# 05_-_Gate_Drivers.net
KiCad netlist of a schematic drawn in Altium Designer
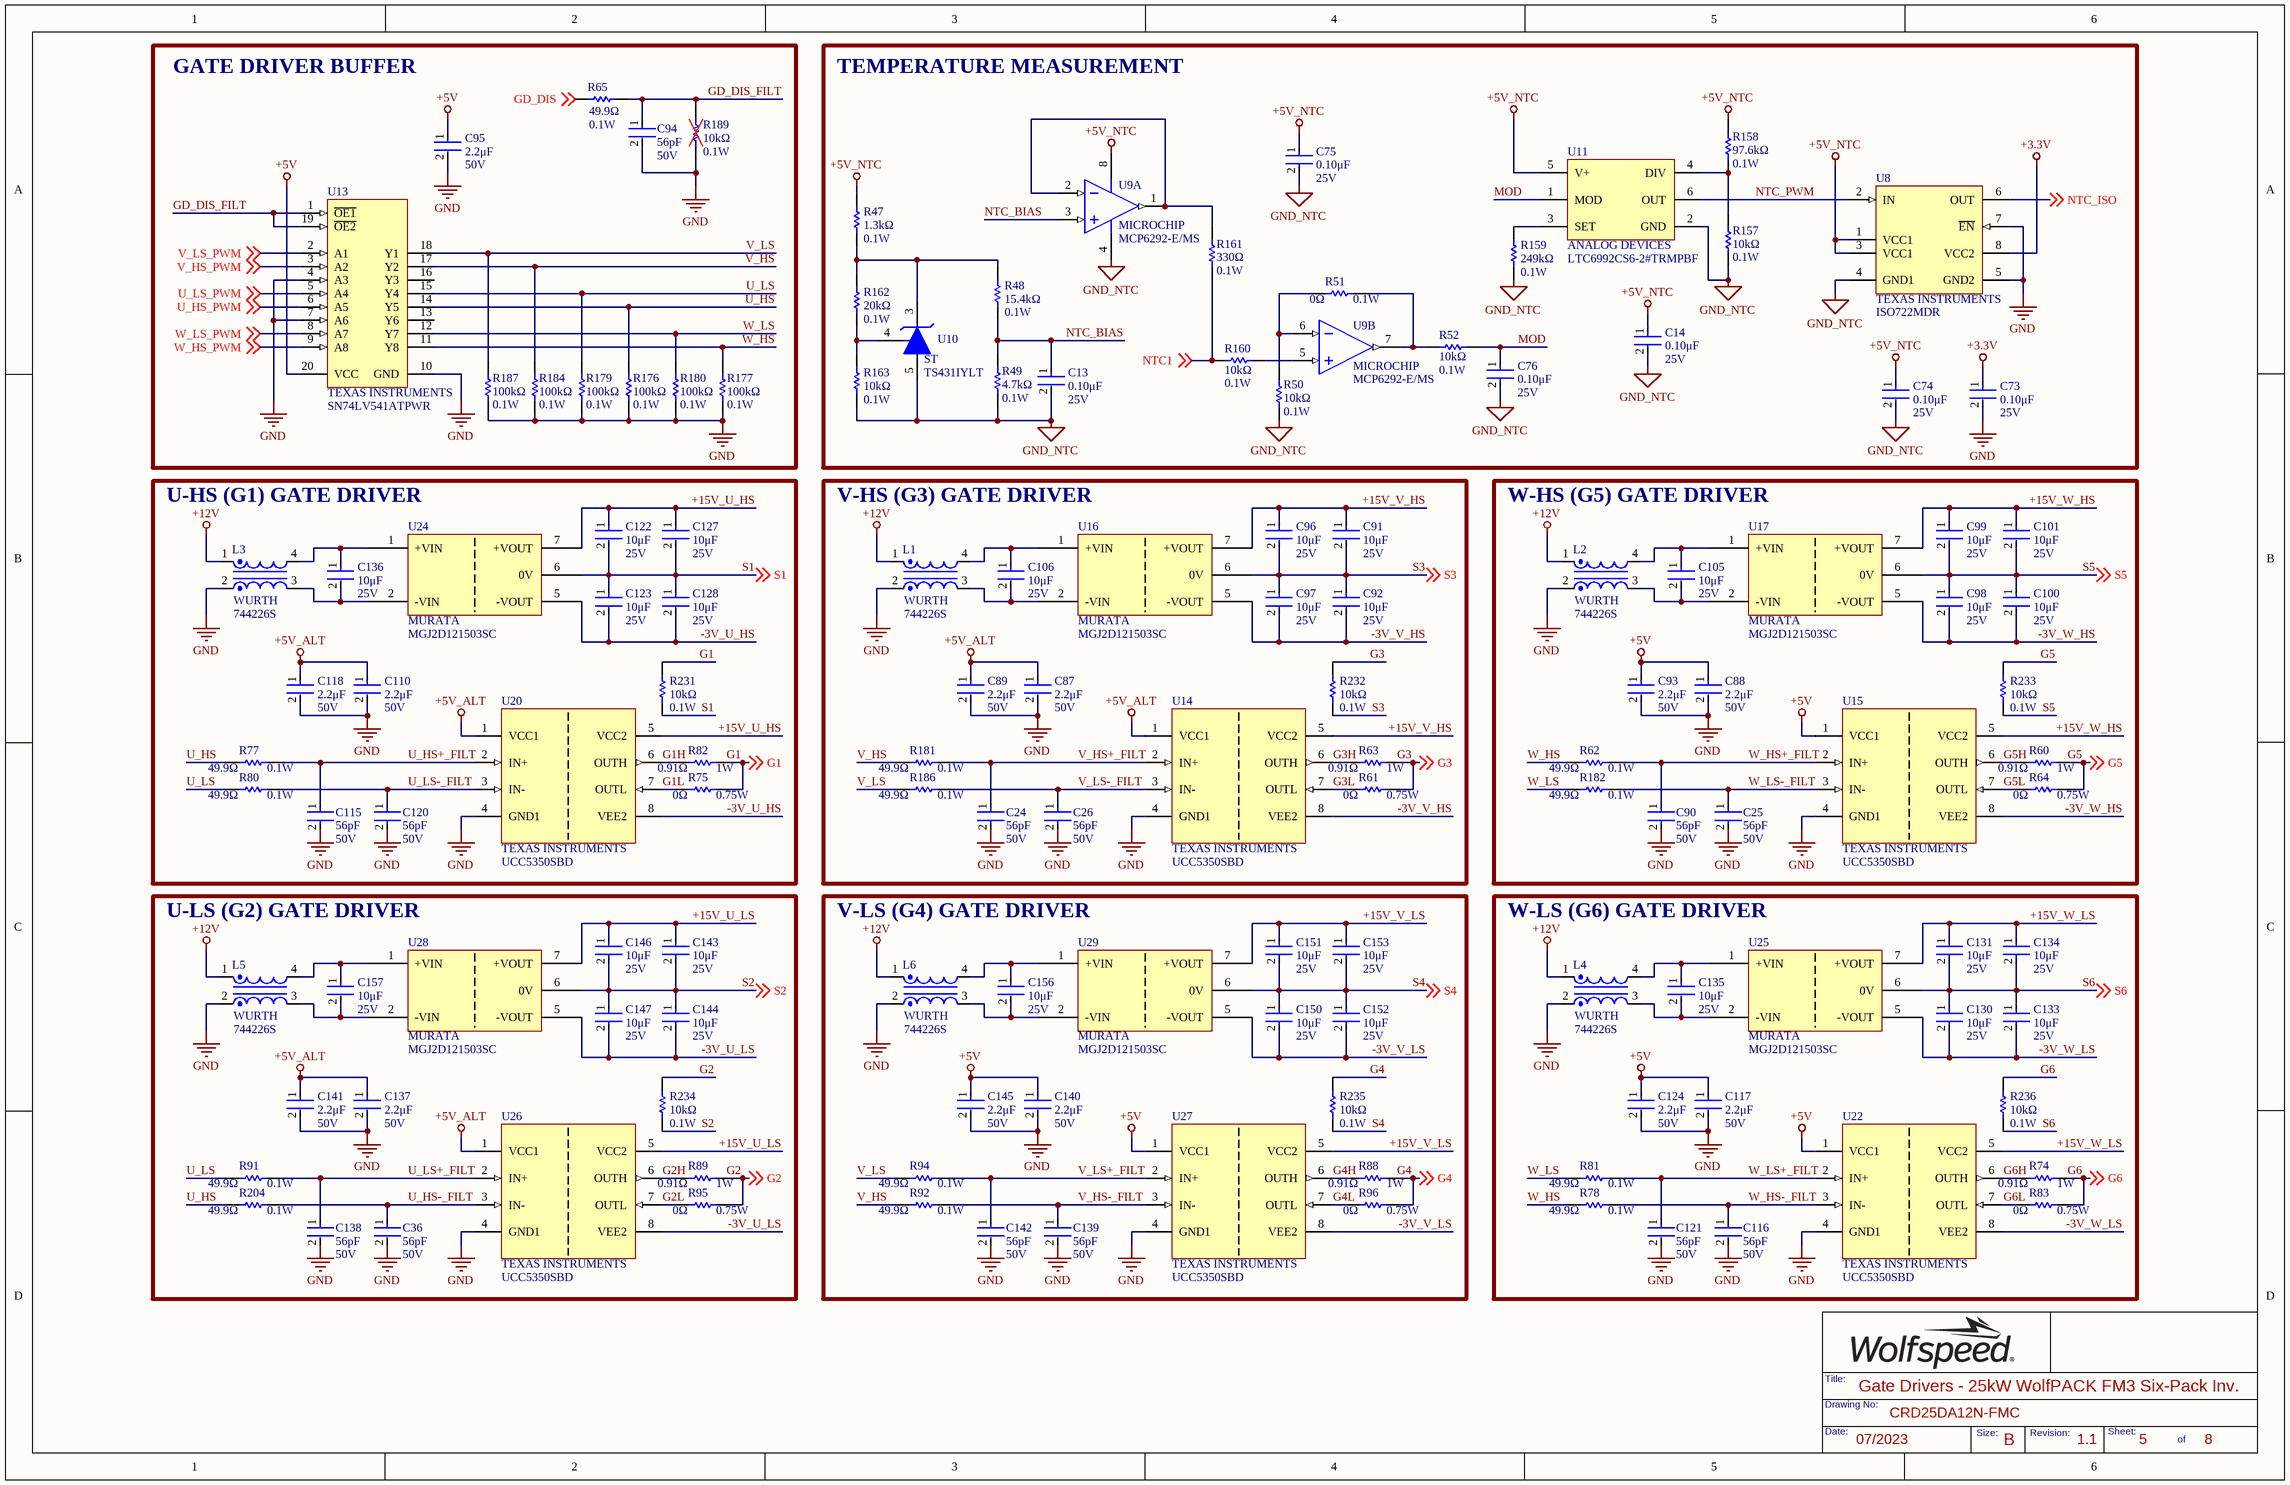
[diagram p0: 05 - Gate Drivers.SchDoc]

(export (version "E")
  (design (tool "Eeschema 10.0.6"))
  (components
    (comp (ref "C13")
      (value "C0603C104K3RACTU")
      (footprint "FP-C0603C-CF-IPC_B")
      (description "CAP CER 0.1UF 25V X7R 0603")
      (fields
        (field (name "VOLTAGE RATING") "25V")
        (field (name "OCTOPART") "https://octopart.com/c0603c104k3ractu-kemet-127541")
        (field (name "MANUFACTURER") "KEMET")
        (field (name "CAPACITANCE") "0.10μF")
      )
      (libsource (lib "Altium Content Vault") (part "b4654b650e69147ec39a6b967a45e02"))
    )
    (comp (ref "C14")
      (value "C0603C104K3RACTU")
      (footprint "FP-C0603C-CF-IPC_B")
      (description "CAP CER 0.1UF 25V X7R 0603")
      (fields
        (field (name "VOLTAGE RATING") "25V")
        (field (name "OCTOPART") "https://octopart.com/c0603c104k3ractu-kemet-127541")
        (field (name "MANUFACTURER") "KEMET")
        (field (name "CAPACITANCE") "0.10μF")
      )
      (libsource (lib "Altium Content Vault") (part "b4654b650e69147ec39a6b967a45e02"))
    )
    (comp (ref "C24")
      (value "CL10C560JB8NNNC")
      (footprint "FP-C0603C-CF-IPC_B")
      (description "CAP CER 56PF 50V C0G/NP0 0603")
      (fields
        (field (name "MANUFACTURER") "SAMSUNG")
        (field (name "TOLERANCE") "5%")
        (field (name "CAPACITANCE") "56pF")
        (field (name "VOLTAGE RATING") "50V")
      )
      (libsource (lib "Inverter_25kW") (part "CL10C560JB8NNNC"))
    )
    (comp (ref "C25")
      (value "CL10C560JB8NNNC")
      (footprint "FP-C0603C-CF-IPC_B")
      (description "CAP CER 56PF 50V C0G/NP0 0603")
      (fields
        (field (name "MANUFACTURER") "SAMSUNG")
        (field (name "TOLERANCE") "5%")
        (field (name "CAPACITANCE") "56pF")
        (field (name "VOLTAGE RATING") "50V")
      )
      (libsource (lib "Inverter_25kW") (part "CL10C560JB8NNNC"))
    )
    (comp (ref "C26")
      (value "CL10C560JB8NNNC")
      (footprint "FP-C0603C-CF-IPC_B")
      (description "CAP CER 56PF 50V C0G/NP0 0603")
      (fields
        (field (name "MANUFACTURER") "SAMSUNG")
        (field (name "TOLERANCE") "5%")
        (field (name "CAPACITANCE") "56pF")
        (field (name "VOLTAGE RATING") "50V")
      )
      (libsource (lib "Inverter_25kW") (part "CL10C560JB8NNNC"))
    )
    (comp (ref "C36")
      (value "CL10C560JB8NNNC")
      (footprint "FP-C0603C-CF-IPC_B")
      (description "CAP CER 56PF 50V C0G/NP0 0603")
      (fields
        (field (name "MANUFACTURER") "SAMSUNG")
        (field (name "TOLERANCE") "5%")
        (field (name "CAPACITANCE") "56pF")
        (field (name "VOLTAGE RATING") "50V")
      )
      (libsource (lib "Inverter_25kW") (part "CL10C560JB8NNNC"))
    )
    (comp (ref "C73")
      (value "C0603C104K3RACTU")
      (footprint "FP-C0603C-CF-IPC_B")
      (description "CAP CER 0.1UF 25V X7R 0603")
      (fields
        (field (name "VOLTAGE RATING") "25V")
        (field (name "OCTOPART") "https://octopart.com/c0603c104k3ractu-kemet-127541")
        (field (name "MANUFACTURER") "KEMET")
        (field (name "CAPACITANCE") "0.10μF")
      )
      (libsource (lib "Altium Content Vault") (part "b4654b650e69147ec39a6b967a45e02"))
    )
    (comp (ref "C74")
      (value "C0603C104K3RACTU")
      (footprint "FP-C0603C-CF-IPC_B")
      (description "CAP CER 0.1UF 25V X7R 0603")
      (fields
        (field (name "VOLTAGE RATING") "25V")
        (field (name "OCTOPART") "https://octopart.com/c0603c104k3ractu-kemet-127541")
        (field (name "MANUFACTURER") "KEMET")
        (field (name "CAPACITANCE") "0.10μF")
      )
      (libsource (lib "Altium Content Vault") (part "b4654b650e69147ec39a6b967a45e02"))
    )
    (comp (ref "C75")
      (value "C0603C104K3RACTU")
      (footprint "FP-C0603C-CF-IPC_B")
      (description "CAP CER 0.1UF 25V X7R 0603")
      (fields
        (field (name "VOLTAGE RATING") "25V")
        (field (name "OCTOPART") "https://octopart.com/c0603c104k3ractu-kemet-127541")
        (field (name "MANUFACTURER") "KEMET")
        (field (name "CAPACITANCE") "0.10μF")
      )
      (libsource (lib "Altium Content Vault") (part "b4654b650e69147ec39a6b967a45e02"))
    )
    (comp (ref "C76")
      (value "C0603C104K3RACTU")
      (footprint "FP-C0603C-CF-IPC_B")
      (description "CAP CER 0.1UF 25V X7R 0603")
      (fields
        (field (name "VOLTAGE RATING") "25V")
        (field (name "OCTOPART") "https://octopart.com/c0603c104k3ractu-kemet-127541")
        (field (name "MANUFACTURER") "KEMET")
        (field (name "CAPACITANCE") "0.10μF")
      )
      (libsource (lib "Altium Content Vault") (part "b4654b650e69147ec39a6b967a45e02"))
    )
    (comp (ref "C87")
      (value "GRT188R61H225ME13D")
      (footprint "FP-C0603C-CF-IPC_B")
      (description "CAP CER 2.2UF 50V X5R 0603")
      (fields
        (field (name "MANUFACTURER") "MURATA")
        (field (name "TOLERANCE") "20%")
        (field (name "VOLTAGE RATING") "50V")
        (field (name "CAPACITANCE") "2.2μF")
      )
      (libsource (lib "Inverter_25kW") (part "GRT188R61H225ME13D"))
    )
    (comp (ref "C88")
      (value "GRT188R61H225ME13D")
      (footprint "FP-C0603C-CF-IPC_B")
      (description "CAP CER 2.2UF 50V X5R 0603")
      (fields
        (field (name "MANUFACTURER") "MURATA")
        (field (name "TOLERANCE") "20%")
        (field (name "VOLTAGE RATING") "50V")
        (field (name "CAPACITANCE") "2.2μF")
      )
      (libsource (lib "Inverter_25kW") (part "GRT188R61H225ME13D"))
    )
    (comp (ref "C89")
      (value "GRT188R61H225ME13D")
      (footprint "FP-C0603C-CF-IPC_B")
      (description "CAP CER 2.2UF 50V X5R 0603")
      (fields
        (field (name "MANUFACTURER") "MURATA")
        (field (name "TOLERANCE") "20%")
        (field (name "VOLTAGE RATING") "50V")
        (field (name "CAPACITANCE") "2.2μF")
      )
      (libsource (lib "Inverter_25kW") (part "GRT188R61H225ME13D"))
    )
    (comp (ref "C90")
      (value "CL10C560JB8NNNC")
      (footprint "FP-C0603C-CF-IPC_B")
      (description "CAP CER 56PF 50V C0G/NP0 0603")
      (fields
        (field (name "MANUFACTURER") "SAMSUNG")
        (field (name "TOLERANCE") "5%")
        (field (name "CAPACITANCE") "56pF")
        (field (name "VOLTAGE RATING") "50V")
      )
      (libsource (lib "Inverter_25kW") (part "CL10C560JB8NNNC"))
    )
    (comp (ref "C91")
      (value "CL31B106KAHSFNE")
      (footprint "FP-CL31-IPC_B")
      (description "CAP CER 10UF 25V X7R 1206")
      (fields
        (field (name "VOLTAGE RATING") "25V")
        (field (name "TOLERANCE") "10%")
        (field (name "CAPACITANCE") "10μF")
        (field (name "MANUFACTURER") "SAMSUNG")
      )
      (libsource (lib "Altium Content Vault") (part "b4654b650e69147ec39a6b967a45e02"))
    )
    (comp (ref "C92")
      (value "CL31B106KAHSFNE")
      (footprint "FP-CL31-IPC_B")
      (description "CAP CER 10UF 25V X7R 1206")
      (fields
        (field (name "VOLTAGE RATING") "25V")
        (field (name "TOLERANCE") "10%")
        (field (name "CAPACITANCE") "10μF")
        (field (name "MANUFACTURER") "SAMSUNG")
      )
      (libsource (lib "Altium Content Vault") (part "b4654b650e69147ec39a6b967a45e02"))
    )
    (comp (ref "C93")
      (value "GRT188R61H225ME13D")
      (footprint "FP-C0603C-CF-IPC_B")
      (description "CAP CER 2.2UF 50V X5R 0603")
      (fields
        (field (name "MANUFACTURER") "MURATA")
        (field (name "TOLERANCE") "20%")
        (field (name "VOLTAGE RATING") "50V")
        (field (name "CAPACITANCE") "2.2μF")
      )
      (libsource (lib "Inverter_25kW") (part "GRT188R61H225ME13D"))
    )
    (comp (ref "C94")
      (value "CL10C560JB8NNNC")
      (footprint "FP-C0603C-CF-IPC_B")
      (description "CAP CER 56PF 50V C0G/NP0 0603")
      (fields
        (field (name "MANUFACTURER") "SAMSUNG")
        (field (name "TOLERANCE") "5%")
        (field (name "CAPACITANCE") "56pF")
        (field (name "VOLTAGE RATING") "50V")
      )
      (libsource (lib "Inverter_25kW") (part "CL10C560JB8NNNC"))
    )
    (comp (ref "C95")
      (value "GRT188R61H225ME13D")
      (footprint "FP-C0603C-CF-IPC_B")
      (description "CAP CER 2.2UF 50V X5R 0603")
      (fields
        (field (name "MANUFACTURER") "MURATA")
        (field (name "TOLERANCE") "20%")
        (field (name "VOLTAGE RATING") "50V")
        (field (name "CAPACITANCE") "2.2μF")
      )
      (libsource (lib "Inverter_25kW") (part "GRT188R61H225ME13D"))
    )
    (comp (ref "C96")
      (value "CL31B106KAHSFNE")
      (footprint "FP-CL31-IPC_B")
      (description "CAP CER 10UF 25V X7R 1206")
      (fields
        (field (name "VOLTAGE RATING") "25V")
        (field (name "TOLERANCE") "10%")
        (field (name "CAPACITANCE") "10μF")
        (field (name "MANUFACTURER") "SAMSUNG")
      )
      (libsource (lib "Altium Content Vault") (part "b4654b650e69147ec39a6b967a45e02"))
    )
    (comp (ref "C97")
      (value "CL31B106KAHSFNE")
      (footprint "FP-CL31-IPC_B")
      (description "CAP CER 10UF 25V X7R 1206")
      (fields
        (field (name "VOLTAGE RATING") "25V")
        (field (name "TOLERANCE") "10%")
        (field (name "CAPACITANCE") "10μF")
        (field (name "MANUFACTURER") "SAMSUNG")
      )
      (libsource (lib "Altium Content Vault") (part "b4654b650e69147ec39a6b967a45e02"))
    )
    (comp (ref "C98")
      (value "CL31B106KAHSFNE")
      (footprint "FP-CL31-IPC_B")
      (description "CAP CER 10UF 25V X7R 1206")
      (fields
        (field (name "VOLTAGE RATING") "25V")
        (field (name "TOLERANCE") "10%")
        (field (name "CAPACITANCE") "10μF")
        (field (name "MANUFACTURER") "SAMSUNG")
      )
      (libsource (lib "Altium Content Vault") (part "b4654b650e69147ec39a6b967a45e02"))
    )
    (comp (ref "C99")
      (value "CL31B106KAHSFNE")
      (footprint "FP-CL31-IPC_B")
      (description "CAP CER 10UF 25V X7R 1206")
      (fields
        (field (name "VOLTAGE RATING") "25V")
        (field (name "TOLERANCE") "10%")
        (field (name "CAPACITANCE") "10μF")
        (field (name "MANUFACTURER") "SAMSUNG")
      )
      (libsource (lib "Altium Content Vault") (part "b4654b650e69147ec39a6b967a45e02"))
    )
    (comp (ref "C100")
      (value "CL31B106KAHSFNE")
      (footprint "FP-CL31-IPC_B")
      (description "CAP CER 10UF 25V X7R 1206")
      (fields
        (field (name "VOLTAGE RATING") "25V")
        (field (name "TOLERANCE") "10%")
        (field (name "CAPACITANCE") "10μF")
        (field (name "MANUFACTURER") "SAMSUNG")
      )
      (libsource (lib "Altium Content Vault") (part "b4654b650e69147ec39a6b967a45e02"))
    )
    (comp (ref "C101")
      (value "CL31B106KAHSFNE")
      (footprint "FP-CL31-IPC_B")
      (description "CAP CER 10UF 25V X7R 1206")
      (fields
        (field (name "VOLTAGE RATING") "25V")
        (field (name "TOLERANCE") "10%")
        (field (name "CAPACITANCE") "10μF")
        (field (name "MANUFACTURER") "SAMSUNG")
      )
      (libsource (lib "Altium Content Vault") (part "b4654b650e69147ec39a6b967a45e02"))
    )
    (comp (ref "C105")
      (value "CL31B106KAHSFNE")
      (footprint "FP-CL31-IPC_B")
      (description "CAP CER 10UF 25V X7R 1206")
      (fields
        (field (name "VOLTAGE RATING") "25V")
        (field (name "TOLERANCE") "10%")
        (field (name "CAPACITANCE") "10μF")
        (field (name "MANUFACTURER") "SAMSUNG")
      )
      (libsource (lib "Altium Content Vault") (part "b4654b650e69147ec39a6b967a45e02"))
    )
    (comp (ref "C106")
      (value "CL31B106KAHSFNE")
      (footprint "FP-CL31-IPC_B")
      (description "CAP CER 10UF 25V X7R 1206")
      (fields
        (field (name "VOLTAGE RATING") "25V")
        (field (name "TOLERANCE") "10%")
        (field (name "CAPACITANCE") "10μF")
        (field (name "MANUFACTURER") "SAMSUNG")
      )
      (libsource (lib "Altium Content Vault") (part "b4654b650e69147ec39a6b967a45e02"))
    )
    (comp (ref "C110")
      (value "GRT188R61H225ME13D")
      (footprint "FP-C0603C-CF-IPC_B")
      (description "CAP CER 2.2UF 50V X5R 0603")
      (fields
        (field (name "MANUFACTURER") "MURATA")
        (field (name "TOLERANCE") "20%")
        (field (name "VOLTAGE RATING") "50V")
        (field (name "CAPACITANCE") "2.2μF")
      )
      (libsource (lib "Inverter_25kW") (part "GRT188R61H225ME13D"))
    )
    (comp (ref "C115")
      (value "CL10C560JB8NNNC")
      (footprint "FP-C0603C-CF-IPC_B")
      (description "CAP CER 56PF 50V C0G/NP0 0603")
      (fields
        (field (name "MANUFACTURER") "SAMSUNG")
        (field (name "TOLERANCE") "5%")
        (field (name "CAPACITANCE") "56pF")
        (field (name "VOLTAGE RATING") "50V")
      )
      (libsource (lib "Inverter_25kW") (part "CL10C560JB8NNNC"))
    )
    (comp (ref "C116")
      (value "CL10C560JB8NNNC")
      (footprint "FP-C0603C-CF-IPC_B")
      (description "CAP CER 56PF 50V C0G/NP0 0603")
      (fields
        (field (name "MANUFACTURER") "SAMSUNG")
        (field (name "TOLERANCE") "5%")
        (field (name "CAPACITANCE") "56pF")
        (field (name "VOLTAGE RATING") "50V")
      )
      (libsource (lib "Inverter_25kW") (part "CL10C560JB8NNNC"))
    )
    (comp (ref "C117")
      (value "GRT188R61H225ME13D")
      (footprint "FP-C0603C-CF-IPC_B")
      (description "CAP CER 2.2UF 50V X5R 0603")
      (fields
        (field (name "MANUFACTURER") "MURATA")
        (field (name "TOLERANCE") "20%")
        (field (name "VOLTAGE RATING") "50V")
        (field (name "CAPACITANCE") "2.2μF")
      )
      (libsource (lib "Inverter_25kW") (part "GRT188R61H225ME13D"))
    )
    (comp (ref "C118")
      (value "GRT188R61H225ME13D")
      (footprint "FP-C0603C-CF-IPC_B")
      (description "CAP CER 2.2UF 50V X5R 0603")
      (fields
        (field (name "MANUFACTURER") "MURATA")
        (field (name "TOLERANCE") "20%")
        (field (name "VOLTAGE RATING") "50V")
        (field (name "CAPACITANCE") "2.2μF")
      )
      (libsource (lib "Inverter_25kW") (part "GRT188R61H225ME13D"))
    )
    (comp (ref "C120")
      (value "CL10C560JB8NNNC")
      (footprint "FP-C0603C-CF-IPC_B")
      (description "CAP CER 56PF 50V C0G/NP0 0603")
      (fields
        (field (name "MANUFACTURER") "SAMSUNG")
        (field (name "TOLERANCE") "5%")
        (field (name "CAPACITANCE") "56pF")
        (field (name "VOLTAGE RATING") "50V")
      )
      (libsource (lib "Inverter_25kW") (part "CL10C560JB8NNNC"))
    )
    (comp (ref "C121")
      (value "CL10C560JB8NNNC")
      (footprint "FP-C0603C-CF-IPC_B")
      (description "CAP CER 56PF 50V C0G/NP0 0603")
      (fields
        (field (name "MANUFACTURER") "SAMSUNG")
        (field (name "TOLERANCE") "5%")
        (field (name "CAPACITANCE") "56pF")
        (field (name "VOLTAGE RATING") "50V")
      )
      (libsource (lib "Inverter_25kW") (part "CL10C560JB8NNNC"))
    )
    (comp (ref "C122")
      (value "CL31B106KAHSFNE")
      (footprint "FP-CL31-IPC_B")
      (description "CAP CER 10UF 25V X7R 1206")
      (fields
        (field (name "VOLTAGE RATING") "25V")
        (field (name "TOLERANCE") "10%")
        (field (name "CAPACITANCE") "10μF")
        (field (name "MANUFACTURER") "SAMSUNG")
      )
      (libsource (lib "Altium Content Vault") (part "b4654b650e69147ec39a6b967a45e02"))
    )
    (comp (ref "C123")
      (value "CL31B106KAHSFNE")
      (footprint "FP-CL31-IPC_B")
      (description "CAP CER 10UF 25V X7R 1206")
      (fields
        (field (name "VOLTAGE RATING") "25V")
        (field (name "TOLERANCE") "10%")
        (field (name "CAPACITANCE") "10μF")
        (field (name "MANUFACTURER") "SAMSUNG")
      )
      (libsource (lib "Altium Content Vault") (part "b4654b650e69147ec39a6b967a45e02"))
    )
    (comp (ref "C124")
      (value "GRT188R61H225ME13D")
      (footprint "FP-C0603C-CF-IPC_B")
      (description "CAP CER 2.2UF 50V X5R 0603")
      (fields
        (field (name "MANUFACTURER") "MURATA")
        (field (name "TOLERANCE") "20%")
        (field (name "VOLTAGE RATING") "50V")
        (field (name "CAPACITANCE") "2.2μF")
      )
      (libsource (lib "Inverter_25kW") (part "GRT188R61H225ME13D"))
    )
    (comp (ref "C127")
      (value "CL31B106KAHSFNE")
      (footprint "FP-CL31-IPC_B")
      (description "CAP CER 10UF 25V X7R 1206")
      (fields
        (field (name "VOLTAGE RATING") "25V")
        (field (name "TOLERANCE") "10%")
        (field (name "CAPACITANCE") "10μF")
        (field (name "MANUFACTURER") "SAMSUNG")
      )
      (libsource (lib "Altium Content Vault") (part "b4654b650e69147ec39a6b967a45e02"))
    )
    (comp (ref "C128")
      (value "CL31B106KAHSFNE")
      (footprint "FP-CL31-IPC_B")
      (description "CAP CER 10UF 25V X7R 1206")
      (fields
        (field (name "VOLTAGE RATING") "25V")
        (field (name "TOLERANCE") "10%")
        (field (name "CAPACITANCE") "10μF")
        (field (name "MANUFACTURER") "SAMSUNG")
      )
      (libsource (lib "Altium Content Vault") (part "b4654b650e69147ec39a6b967a45e02"))
    )
    (comp (ref "C130")
      (value "CL31B106KAHSFNE")
      (footprint "FP-CL31-IPC_B")
      (description "CAP CER 10UF 25V X7R 1206")
      (fields
        (field (name "VOLTAGE RATING") "25V")
        (field (name "TOLERANCE") "10%")
        (field (name "CAPACITANCE") "10μF")
        (field (name "MANUFACTURER") "SAMSUNG")
      )
      (libsource (lib "Altium Content Vault") (part "b4654b650e69147ec39a6b967a45e02"))
    )
    (comp (ref "C131")
      (value "CL31B106KAHSFNE")
      (footprint "FP-CL31-IPC_B")
      (description "CAP CER 10UF 25V X7R 1206")
      (fields
        (field (name "VOLTAGE RATING") "25V")
        (field (name "TOLERANCE") "10%")
        (field (name "CAPACITANCE") "10μF")
        (field (name "MANUFACTURER") "SAMSUNG")
      )
      (libsource (lib "Altium Content Vault") (part "b4654b650e69147ec39a6b967a45e02"))
    )
    (comp (ref "C133")
      (value "CL31B106KAHSFNE")
      (footprint "FP-CL31-IPC_B")
      (description "CAP CER 10UF 25V X7R 1206")
      (fields
        (field (name "VOLTAGE RATING") "25V")
        (field (name "TOLERANCE") "10%")
        (field (name "CAPACITANCE") "10μF")
        (field (name "MANUFACTURER") "SAMSUNG")
      )
      (libsource (lib "Altium Content Vault") (part "b4654b650e69147ec39a6b967a45e02"))
    )
    (comp (ref "C134")
      (value "CL31B106KAHSFNE")
      (footprint "FP-CL31-IPC_B")
      (description "CAP CER 10UF 25V X7R 1206")
      (fields
        (field (name "VOLTAGE RATING") "25V")
        (field (name "TOLERANCE") "10%")
        (field (name "CAPACITANCE") "10μF")
        (field (name "MANUFACTURER") "SAMSUNG")
      )
      (libsource (lib "Altium Content Vault") (part "b4654b650e69147ec39a6b967a45e02"))
    )
    (comp (ref "C135")
      (value "CL31B106KAHSFNE")
      (footprint "FP-CL31-IPC_B")
      (description "CAP CER 10UF 25V X7R 1206")
      (fields
        (field (name "VOLTAGE RATING") "25V")
        (field (name "TOLERANCE") "10%")
        (field (name "CAPACITANCE") "10μF")
        (field (name "MANUFACTURER") "SAMSUNG")
      )
      (libsource (lib "Altium Content Vault") (part "b4654b650e69147ec39a6b967a45e02"))
    )
    (comp (ref "C136")
      (value "CL31B106KAHSFNE")
      (footprint "FP-CL31-IPC_B")
      (description "CAP CER 10UF 25V X7R 1206")
      (fields
        (field (name "VOLTAGE RATING") "25V")
        (field (name "TOLERANCE") "10%")
        (field (name "CAPACITANCE") "10μF")
        (field (name "MANUFACTURER") "SAMSUNG")
      )
      (libsource (lib "Altium Content Vault") (part "b4654b650e69147ec39a6b967a45e02"))
    )
    (comp (ref "C137")
      (value "GRT188R61H225ME13D")
      (footprint "FP-C0603C-CF-IPC_B")
      (description "CAP CER 2.2UF 50V X5R 0603")
      (fields
        (field (name "MANUFACTURER") "MURATA")
        (field (name "TOLERANCE") "20%")
        (field (name "VOLTAGE RATING") "50V")
        (field (name "CAPACITANCE") "2.2μF")
      )
      (libsource (lib "Inverter_25kW") (part "GRT188R61H225ME13D"))
    )
    (comp (ref "C138")
      (value "CL10C560JB8NNNC")
      (footprint "FP-C0603C-CF-IPC_B")
      (description "CAP CER 56PF 50V C0G/NP0 0603")
      (fields
        (field (name "MANUFACTURER") "SAMSUNG")
        (field (name "TOLERANCE") "5%")
        (field (name "CAPACITANCE") "56pF")
        (field (name "VOLTAGE RATING") "50V")
      )
      (libsource (lib "Inverter_25kW") (part "CL10C560JB8NNNC"))
    )
    (comp (ref "C139")
      (value "CL10C560JB8NNNC")
      (footprint "FP-C0603C-CF-IPC_B")
      (description "CAP CER 56PF 50V C0G/NP0 0603")
      (fields
        (field (name "MANUFACTURER") "SAMSUNG")
        (field (name "TOLERANCE") "5%")
        (field (name "CAPACITANCE") "56pF")
        (field (name "VOLTAGE RATING") "50V")
      )
      (libsource (lib "Inverter_25kW") (part "CL10C560JB8NNNC"))
    )
    (comp (ref "C140")
      (value "GRT188R61H225ME13D")
      (footprint "FP-C0603C-CF-IPC_B")
      (description "CAP CER 2.2UF 50V X5R 0603")
      (fields
        (field (name "MANUFACTURER") "MURATA")
        (field (name "TOLERANCE") "20%")
        (field (name "VOLTAGE RATING") "50V")
        (field (name "CAPACITANCE") "2.2μF")
      )
      (libsource (lib "Inverter_25kW") (part "GRT188R61H225ME13D"))
    )
    (comp (ref "C141")
      (value "GRT188R61H225ME13D")
      (footprint "FP-C0603C-CF-IPC_B")
      (description "CAP CER 2.2UF 50V X5R 0603")
      (fields
        (field (name "MANUFACTURER") "MURATA")
        (field (name "TOLERANCE") "20%")
        (field (name "VOLTAGE RATING") "50V")
        (field (name "CAPACITANCE") "2.2μF")
      )
      (libsource (lib "Inverter_25kW") (part "GRT188R61H225ME13D"))
    )
    (comp (ref "C142")
      (value "CL10C560JB8NNNC")
      (footprint "FP-C0603C-CF-IPC_B")
      (description "CAP CER 56PF 50V C0G/NP0 0603")
      (fields
        (field (name "MANUFACTURER") "SAMSUNG")
        (field (name "TOLERANCE") "5%")
        (field (name "CAPACITANCE") "56pF")
        (field (name "VOLTAGE RATING") "50V")
      )
      (libsource (lib "Inverter_25kW") (part "CL10C560JB8NNNC"))
    )
    (comp (ref "C143")
      (value "CL31B106KAHSFNE")
      (footprint "FP-CL31-IPC_B")
      (description "CAP CER 10UF 25V X7R 1206")
      (fields
        (field (name "VOLTAGE RATING") "25V")
        (field (name "TOLERANCE") "10%")
        (field (name "CAPACITANCE") "10μF")
        (field (name "MANUFACTURER") "SAMSUNG")
      )
      (libsource (lib "Altium Content Vault") (part "b4654b650e69147ec39a6b967a45e02"))
    )
    (comp (ref "C144")
      (value "CL31B106KAHSFNE")
      (footprint "FP-CL31-IPC_B")
      (description "CAP CER 10UF 25V X7R 1206")
      (fields
        (field (name "VOLTAGE RATING") "25V")
        (field (name "TOLERANCE") "10%")
        (field (name "CAPACITANCE") "10μF")
        (field (name "MANUFACTURER") "SAMSUNG")
      )
      (libsource (lib "Altium Content Vault") (part "b4654b650e69147ec39a6b967a45e02"))
    )
    (comp (ref "C145")
      (value "GRT188R61H225ME13D")
      (footprint "FP-C0603C-CF-IPC_B")
      (description "CAP CER 2.2UF 50V X5R 0603")
      (fields
        (field (name "MANUFACTURER") "MURATA")
        (field (name "TOLERANCE") "20%")
        (field (name "VOLTAGE RATING") "50V")
        (field (name "CAPACITANCE") "2.2μF")
      )
      (libsource (lib "Inverter_25kW") (part "GRT188R61H225ME13D"))
    )
    (comp (ref "C146")
      (value "CL31B106KAHSFNE")
      (footprint "FP-CL31-IPC_B")
      (description "CAP CER 10UF 25V X7R 1206")
      (fields
        (field (name "VOLTAGE RATING") "25V")
        (field (name "TOLERANCE") "10%")
        (field (name "CAPACITANCE") "10μF")
        (field (name "MANUFACTURER") "SAMSUNG")
      )
      (libsource (lib "Altium Content Vault") (part "b4654b650e69147ec39a6b967a45e02"))
    )
    (comp (ref "C147")
      (value "CL31B106KAHSFNE")
      (footprint "FP-CL31-IPC_B")
      (description "CAP CER 10UF 25V X7R 1206")
      (fields
        (field (name "VOLTAGE RATING") "25V")
        (field (name "TOLERANCE") "10%")
        (field (name "CAPACITANCE") "10μF")
        (field (name "MANUFACTURER") "SAMSUNG")
      )
      (libsource (lib "Altium Content Vault") (part "b4654b650e69147ec39a6b967a45e02"))
    )
    (comp (ref "C150")
      (value "CL31B106KAHSFNE")
      (footprint "FP-CL31-IPC_B")
      (description "CAP CER 10UF 25V X7R 1206")
      (fields
        (field (name "VOLTAGE RATING") "25V")
        (field (name "TOLERANCE") "10%")
        (field (name "CAPACITANCE") "10μF")
        (field (name "MANUFACTURER") "SAMSUNG")
      )
      (libsource (lib "Altium Content Vault") (part "b4654b650e69147ec39a6b967a45e02"))
    )
    (comp (ref "C151")
      (value "CL31B106KAHSFNE")
      (footprint "FP-CL31-IPC_B")
      (description "CAP CER 10UF 25V X7R 1206")
      (fields
        (field (name "VOLTAGE RATING") "25V")
        (field (name "TOLERANCE") "10%")
        (field (name "CAPACITANCE") "10μF")
        (field (name "MANUFACTURER") "SAMSUNG")
      )
      (libsource (lib "Altium Content Vault") (part "b4654b650e69147ec39a6b967a45e02"))
    )
    (comp (ref "C152")
      (value "CL31B106KAHSFNE")
      (footprint "FP-CL31-IPC_B")
      (description "CAP CER 10UF 25V X7R 1206")
      (fields
        (field (name "VOLTAGE RATING") "25V")
        (field (name "TOLERANCE") "10%")
        (field (name "CAPACITANCE") "10μF")
        (field (name "MANUFACTURER") "SAMSUNG")
      )
      (libsource (lib "Altium Content Vault") (part "b4654b650e69147ec39a6b967a45e02"))
    )
    (comp (ref "C153")
      (value "CL31B106KAHSFNE")
      (footprint "FP-CL31-IPC_B")
      (description "CAP CER 10UF 25V X7R 1206")
      (fields
        (field (name "VOLTAGE RATING") "25V")
        (field (name "TOLERANCE") "10%")
        (field (name "CAPACITANCE") "10μF")
        (field (name "MANUFACTURER") "SAMSUNG")
      )
      (libsource (lib "Altium Content Vault") (part "b4654b650e69147ec39a6b967a45e02"))
    )
    (comp (ref "C156")
      (value "CL31B106KAHSFNE")
      (footprint "FP-CL31-IPC_B")
      (description "CAP CER 10UF 25V X7R 1206")
      (fields
        (field (name "VOLTAGE RATING") "25V")
        (field (name "TOLERANCE") "10%")
        (field (name "CAPACITANCE") "10μF")
        (field (name "MANUFACTURER") "SAMSUNG")
      )
      (libsource (lib "Altium Content Vault") (part "b4654b650e69147ec39a6b967a45e02"))
    )
    (comp (ref "C157")
      (value "CL31B106KAHSFNE")
      (footprint "FP-CL31-IPC_B")
      (description "CAP CER 10UF 25V X7R 1206")
      (fields
        (field (name "VOLTAGE RATING") "25V")
        (field (name "TOLERANCE") "10%")
        (field (name "CAPACITANCE") "10μF")
        (field (name "MANUFACTURER") "SAMSUNG")
      )
      (libsource (lib "Altium Content Vault") (part "b4654b650e69147ec39a6b967a45e02"))
    )
    (comp (ref "L1")
      (value "744226S")
      (footprint "Inverter_25kW:WE-SL2")
      (description "CMC 10UH 1.6A 2LN 920 OHM SMD")
      (fields
        (field (name "MANUFACTURER") "WURTH ELECTRONIK")
        (field (name "TOLERANCE") "30%")
        (field (name "MANUFACTURER PRINT") "WURTH")
      )
      (libsource (lib "Inverter_25kW") (part "744226S"))
    )
    (comp (ref "L2")
      (value "744226S")
      (footprint "Inverter_25kW:WE-SL2")
      (description "CMC 10UH 1.6A 2LN 920 OHM SMD")
      (fields
        (field (name "MANUFACTURER") "WURTH ELECTRONIK")
        (field (name "TOLERANCE") "30%")
        (field (name "MANUFACTURER PRINT") "WURTH")
      )
      (libsource (lib "Inverter_25kW") (part "744226S"))
    )
    (comp (ref "L3")
      (value "744226S")
      (footprint "Inverter_25kW:WE-SL2")
      (description "CMC 10UH 1.6A 2LN 920 OHM SMD")
      (fields
        (field (name "MANUFACTURER") "WURTH ELECTRONIK")
        (field (name "TOLERANCE") "30%")
        (field (name "MANUFACTURER PRINT") "WURTH")
      )
      (libsource (lib "Inverter_25kW") (part "744226S"))
    )
    (comp (ref "L4")
      (value "744226S")
      (footprint "Inverter_25kW:WE-SL2")
      (description "CMC 10UH 1.6A 2LN 920 OHM SMD")
      (fields
        (field (name "MANUFACTURER") "WURTH ELECTRONIK")
        (field (name "TOLERANCE") "30%")
        (field (name "MANUFACTURER PRINT") "WURTH")
      )
      (libsource (lib "Inverter_25kW") (part "744226S"))
    )
    (comp (ref "L5")
      (value "744226S")
      (footprint "Inverter_25kW:WE-SL2")
      (description "CMC 10UH 1.6A 2LN 920 OHM SMD")
      (fields
        (field (name "MANUFACTURER") "WURTH ELECTRONIK")
        (field (name "TOLERANCE") "30%")
        (field (name "MANUFACTURER PRINT") "WURTH")
      )
      (libsource (lib "Inverter_25kW") (part "744226S"))
    )
    (comp (ref "L6")
      (value "744226S")
      (footprint "Inverter_25kW:WE-SL2")
      (description "CMC 10UH 1.6A 2LN 920 OHM SMD")
      (fields
        (field (name "MANUFACTURER") "WURTH ELECTRONIK")
        (field (name "TOLERANCE") "30%")
        (field (name "MANUFACTURER PRINT") "WURTH")
      )
      (libsource (lib "Inverter_25kW") (part "744226S"))
    )
    (comp (ref "R47")
      (value "ERA3AEB132V")
      (footprint "FP-MCR03-IPC_B")
      (description "RES SMD 1.3K OHM 0.1% 1/10W 0603")
      (fields
        (field (name "MANUFACTURER") "PANASONIC")
        (field (name "MANUFACTURER PART NUMBER") "ERA-3AEB132V")
        (field (name "POWER RATING") "0.1W")
        (field (name "RESISTANCE") "1.3kΩ")
      )
      (libsource (lib "Inverter_25kW") (part "ERA3AEB132V"))
    )
    (comp (ref "R48")
      (value "RC1608F1542CS")
      (footprint "FP-MCR03-IPC_B")
      (description "RES SMD 15.4K OHM 1% 1/10W 0603")
      (fields
        (field (name "MANUFACTURER") "SAMSUNG")
        (field (name "TOLERANCE") "1%")
        (field (name "POWER RATING") "0.1W")
        (field (name "RESISTANCE") "15.4kΩ")
      )
      (libsource (lib "Inverter_25kW") (part "RC1608F1542CS"))
    )
    (comp (ref "R49")
      (value "CRCW06034K70FKTA")
      (footprint "FP-MCR03-IPC_B")
      (description "RES SMD 4.7K OHM 1% 1/10W 0603")
      (fields
        (field (name "MANUFACTURER") "VISHAY DALE")
        (field (name "TOLERANCE") "1%")
        (field (name "RESISTANCE") "4.7kΩ")
        (field (name "POWER RATING") "0.1W")
      )
      (libsource (lib "Inverter_25kW") (part "CRCW06034K70FKTA"))
    )
    (comp (ref "R50")
      (value "ERJ3EKF1002V")
      (footprint "FP-MCR03-IPC_B")
      (description "RES SMD 10K OHM 1% 1/10W 0603")
      (fields
        (field (name "MANUFACTURER") "PANASONIC")
        (field (name "MANUFACTURER PART NUMBER") "ERJ-3EKF1002V")
        (field (name "RESISTANCE") "10kΩ")
        (field (name "MAX POWER DISSIPATION") "0.1W")
      )
      (libsource (lib "Inverter_25kW") (part "ERJ3EKF1002V"))
    )
    (comp (ref "R51")
      (value "CRCW06030000Z0EB")
      (footprint "FP-MCR03-IPC_B")
      (description "RES SMD 0 OHM JUMPER 1/10W 0603")
      (fields
        (field (name "MANUFACTURER") "VISHAY DALE")
        (field (name "MANUFACTURER PART NUMBER") "CRCW06030000Z0EBC")
        (field (name "RESISTANCE") "0Ω")
        (field (name "POWER RATING") "0.1W")
      )
      (libsource (lib "Inverter_25kW") (part "CRCW06030000Z0EB"))
    )
    (comp (ref "R52")
      (value "ERJ3EKF1002V")
      (footprint "FP-MCR03-IPC_B")
      (description "RES SMD 10K OHM 1% 1/10W 0603")
      (fields
        (field (name "MANUFACTURER") "PANASONIC")
        (field (name "MANUFACTURER PART NUMBER") "ERJ-3EKF1002V")
        (field (name "RESISTANCE") "10kΩ")
        (field (name "MAX POWER DISSIPATION") "0.1W")
      )
      (libsource (lib "Inverter_25kW") (part "ERJ3EKF1002V"))
    )
    (comp (ref "R60")
      (value "0.91Ω")
      (footprint "RESC3125X70X40NL20T20")
      (description "RES 0.91 OHM 1% 1W 1210")
      (fields
        (field (name "MANUFACTURER") "VISHAY DALE")
        (field (name "PART NUMBER") "RCWE1210R910FKEA")
        (field (name "POWER") "1W")
      )
      (libsource (lib "Altium Content Vault") (part "RES"))
    )
    (comp (ref "R61")
      (value "0Ω")
      (footprint "RESC3125X70X40NL20T20")
      (description "RES SMD 0 OHM JUMPER 3/4W 1210")
      (fields
        (field (name "MANUFACTURER") "VISHAY DALE")
        (field (name "MANUFACTURER PART NUMBER") "CRCW12100000Z0EAHP")
        (field (name "POWER RATING") "0.75W")
      )
      (libsource (lib "CRD25DA12N-FMC") (part "CRCW12100000Z0EAHP"))
    )
    (comp (ref "R62")
      (value "ERJ-3EKF49R9V")
      (footprint "FP-MCR03-IPC_B")
      (description "RES SMD 49.9 OHM 1% 1/10W 0603")
      (fields
        (field (name "MANUFACTURER") "PANASONIC")
        (field (name "TOLERANCE") "1%")
        (field (name "RESISTANCE") "49.9Ω")
        (field (name "POWER RATING") "0.1W")
      )
      (libsource (lib "Inverter_25kW") (part "ERJ-3EKF49R9V"))
    )
    (comp (ref "R63")
      (value "0.91Ω")
      (footprint "RESC3125X70X40NL20T20")
      (description "RES 0.91 OHM 1% 1W 1210")
      (fields
        (field (name "MANUFACTURER") "VISHAY DALE")
        (field (name "PART NUMBER") "RCWE1210R910FKEA")
        (field (name "POWER") "1W")
      )
      (libsource (lib "Altium Content Vault") (part "RES"))
    )
    (comp (ref "R64")
      (value "0Ω")
      (footprint "RESC3125X70X40NL20T20")
      (description "RES SMD 0 OHM JUMPER 3/4W 1210")
      (fields
        (field (name "MANUFACTURER") "VISHAY DALE")
        (field (name "MANUFACTURER PART NUMBER") "CRCW12100000Z0EAHP")
        (field (name "POWER RATING") "0.75W")
      )
      (libsource (lib "CRD25DA12N-FMC") (part "CRCW12100000Z0EAHP"))
    )
    (comp (ref "R65")
      (value "ERJ-3EKF49R9V")
      (footprint "FP-MCR03-IPC_B")
      (description "RES SMD 49.9 OHM 1% 1/10W 0603")
      (fields
        (field (name "MANUFACTURER") "PANASONIC")
        (field (name "TOLERANCE") "1%")
        (field (name "RESISTANCE") "49.9Ω")
        (field (name "POWER RATING") "0.1W")
      )
      (libsource (lib "Inverter_25kW") (part "ERJ-3EKF49R9V"))
    )
    (comp (ref "R74")
      (value "0.91Ω")
      (footprint "RESC3125X70X40NL20T20")
      (description "RES 0.91 OHM 1% 1W 1210")
      (fields
        (field (name "MANUFACTURER") "VISHAY DALE")
        (field (name "PART NUMBER") "RCWE1210R910FKEA")
        (field (name "POWER") "1W")
      )
      (libsource (lib "Altium Content Vault") (part "RES"))
    )
    (comp (ref "R75")
      (value "0Ω")
      (footprint "RESC3125X70X40NL20T20")
      (description "RES SMD 0 OHM JUMPER 3/4W 1210")
      (fields
        (field (name "MANUFACTURER") "VISHAY DALE")
        (field (name "MANUFACTURER PART NUMBER") "CRCW12100000Z0EAHP")
        (field (name "POWER RATING") "0.75W")
      )
      (libsource (lib "CRD25DA12N-FMC") (part "CRCW12100000Z0EAHP"))
    )
    (comp (ref "R77")
      (value "ERJ-3EKF49R9V")
      (footprint "FP-MCR03-IPC_B")
      (description "RES SMD 49.9 OHM 1% 1/10W 0603")
      (fields
        (field (name "MANUFACTURER") "PANASONIC")
        (field (name "TOLERANCE") "1%")
        (field (name "RESISTANCE") "49.9Ω")
        (field (name "POWER RATING") "0.1W")
      )
      (libsource (lib "Inverter_25kW") (part "ERJ-3EKF49R9V"))
    )
    (comp (ref "R78")
      (value "ERJ-3EKF49R9V")
      (footprint "FP-MCR03-IPC_B")
      (description "RES SMD 49.9 OHM 1% 1/10W 0603")
      (fields
        (field (name "MANUFACTURER") "PANASONIC")
        (field (name "TOLERANCE") "1%")
        (field (name "RESISTANCE") "49.9Ω")
        (field (name "POWER RATING") "0.1W")
      )
      (libsource (lib "Inverter_25kW") (part "ERJ-3EKF49R9V"))
    )
    (comp (ref "R80")
      (value "ERJ-3EKF49R9V")
      (footprint "FP-MCR03-IPC_B")
      (description "RES SMD 49.9 OHM 1% 1/10W 0603")
      (fields
        (field (name "MANUFACTURER") "PANASONIC")
        (field (name "TOLERANCE") "1%")
        (field (name "RESISTANCE") "49.9Ω")
        (field (name "POWER RATING") "0.1W")
      )
      (libsource (lib "Inverter_25kW") (part "ERJ-3EKF49R9V"))
    )
    (comp (ref "R81")
      (value "ERJ-3EKF49R9V")
      (footprint "FP-MCR03-IPC_B")
      (description "RES SMD 49.9 OHM 1% 1/10W 0603")
      (fields
        (field (name "MANUFACTURER") "PANASONIC")
        (field (name "TOLERANCE") "1%")
        (field (name "RESISTANCE") "49.9Ω")
        (field (name "POWER RATING") "0.1W")
      )
      (libsource (lib "Inverter_25kW") (part "ERJ-3EKF49R9V"))
    )
    (comp (ref "R82")
      (value "0.91Ω")
      (footprint "RESC3125X70X40NL20T20")
      (description "RES 0.91 OHM 1% 1W 1210")
      (fields
        (field (name "MANUFACTURER") "VISHAY DALE")
        (field (name "PART NUMBER") "RCWE1210R910FKEA")
        (field (name "POWER") "1W")
      )
      (libsource (lib "Altium Content Vault") (part "RES"))
    )
    (comp (ref "R83")
      (value "0Ω")
      (footprint "RESC3125X70X40NL20T20")
      (description "RES SMD 0 OHM JUMPER 3/4W 1210")
      (fields
        (field (name "MANUFACTURER") "VISHAY DALE")
        (field (name "MANUFACTURER PART NUMBER") "CRCW12100000Z0EAHP")
        (field (name "POWER RATING") "0.75W")
      )
      (libsource (lib "CRD25DA12N-FMC") (part "CRCW12100000Z0EAHP"))
    )
    (comp (ref "R88")
      (value "0.91Ω")
      (footprint "RESC3125X70X40NL20T20")
      (description "RES 0.91 OHM 1% 1W 1210")
      (fields
        (field (name "MANUFACTURER") "VISHAY DALE")
        (field (name "PART NUMBER") "RCWE1210R910FKEA")
        (field (name "POWER") "1W")
      )
      (libsource (lib "Altium Content Vault") (part "RES"))
    )
    (comp (ref "R89")
      (value "0.91Ω")
      (footprint "RESC3125X70X40NL20T20")
      (description "RES 0.91 OHM 1% 1W 1210")
      (fields
        (field (name "MANUFACTURER") "VISHAY DALE")
        (field (name "PART NUMBER") "RCWE1210R910FKEA")
        (field (name "POWER") "1W")
      )
      (libsource (lib "Altium Content Vault") (part "RES"))
    )
    (comp (ref "R91")
      (value "ERJ-3EKF49R9V")
      (footprint "FP-MCR03-IPC_B")
      (description "RES SMD 49.9 OHM 1% 1/10W 0603")
      (fields
        (field (name "MANUFACTURER") "PANASONIC")
        (field (name "TOLERANCE") "1%")
        (field (name "RESISTANCE") "49.9Ω")
        (field (name "POWER RATING") "0.1W")
      )
      (libsource (lib "Inverter_25kW") (part "ERJ-3EKF49R9V"))
    )
    (comp (ref "R92")
      (value "ERJ-3EKF49R9V")
      (footprint "FP-MCR03-IPC_B")
      (description "RES SMD 49.9 OHM 1% 1/10W 0603")
      (fields
        (field (name "MANUFACTURER") "PANASONIC")
        (field (name "TOLERANCE") "1%")
        (field (name "RESISTANCE") "49.9Ω")
        (field (name "POWER RATING") "0.1W")
      )
      (libsource (lib "Inverter_25kW") (part "ERJ-3EKF49R9V"))
    )
    (comp (ref "R94")
      (value "ERJ-3EKF49R9V")
      (footprint "FP-MCR03-IPC_B")
      (description "RES SMD 49.9 OHM 1% 1/10W 0603")
      (fields
        (field (name "MANUFACTURER") "PANASONIC")
        (field (name "TOLERANCE") "1%")
        (field (name "RESISTANCE") "49.9Ω")
        (field (name "POWER RATING") "0.1W")
      )
      (libsource (lib "Inverter_25kW") (part "ERJ-3EKF49R9V"))
    )
    (comp (ref "R95")
      (value "0Ω")
      (footprint "RESC3125X70X40NL20T20")
      (description "RES SMD 0 OHM JUMPER 3/4W 1210")
      (fields
        (field (name "MANUFACTURER") "VISHAY DALE")
        (field (name "MANUFACTURER PART NUMBER") "CRCW12100000Z0EAHP")
        (field (name "POWER RATING") "0.75W")
      )
      (libsource (lib "CRD25DA12N-FMC") (part "CRCW12100000Z0EAHP"))
    )
    (comp (ref "R96")
      (value "0Ω")
      (footprint "RESC3125X70X40NL20T20")
      (description "RES SMD 0 OHM JUMPER 3/4W 1210")
      (fields
        (field (name "MANUFACTURER") "VISHAY DALE")
        (field (name "MANUFACTURER PART NUMBER") "CRCW12100000Z0EAHP")
        (field (name "POWER RATING") "0.75W")
      )
      (libsource (lib "CRD25DA12N-FMC") (part "CRCW12100000Z0EAHP"))
    )
    (comp (ref "R157")
      (value "ERJ3EKF1002V")
      (footprint "FP-MCR03-IPC_B")
      (description "RES SMD 10K OHM 1% 1/10W 0603")
      (fields
        (field (name "MANUFACTURER") "PANASONIC")
        (field (name "MANUFACTURER PART NUMBER") "ERJ-3EKF1002V")
        (field (name "RESISTANCE") "10kΩ")
        (field (name "MAX POWER DISSIPATION") "0.1W")
      )
      (libsource (lib "Inverter_25kW") (part "ERJ3EKF1002V"))
    )
    (comp (ref "R158")
      (value "ERJ-3EKF9762V")
      (footprint "FP-MCR03-IPC_B")
      (description "RES SMD 97.6K OHM 1% 1/10W 0603")
      (fields
        (field (name "MANUFACTURER") "PANASONIC")
        (field (name "TOLERANCE") "1%")
        (field (name "RESISTANCE") "97.6kΩ")
        (field (name "MAX POWER DISSIPATION") "0.1W")
      )
      (libsource (lib "Inverter_25kW") (part "ERJ-3EKF9762V"))
    )
    (comp (ref "R159")
      (value "RMCF0603FT249K")
      (footprint "FP-MCR03-IPC_B")
      (description "RES 249K OHM 1% 1/10W 0603")
      (fields
        (field (name "MANUFACTURER") "STACKPOLE")
        (field (name "TOLERANCE") "1%")
        (field (name "MAX POWER DISSIPATION") "0.1W")
        (field (name "RESISTANCE") "249kΩ")
      )
      (libsource (lib "Inverter_25kW") (part "RMCF0603FT249K"))
    )
    (comp (ref "R160")
      (value "ERJ3EKF1002V")
      (footprint "FP-MCR03-IPC_B")
      (description "RES SMD 10K OHM 1% 1/10W 0603")
      (fields
        (field (name "MANUFACTURER") "PANASONIC")
        (field (name "MANUFACTURER PART NUMBER") "ERJ-3EKF1002V")
        (field (name "RESISTANCE") "10kΩ")
        (field (name "MAX POWER DISSIPATION") "0.1W")
      )
      (libsource (lib "Inverter_25kW") (part "ERJ3EKF1002V"))
    )
    (comp (ref "R161")
      (value "RC0603FR-13330RL")
      (footprint "FP-MCR03-IPC_B")
      (description "RES 330 OHM 1% 1/10W 0603")
      (fields
        (field (name "MANUFACTURER") "YAGEO")
        (field (name "TOLERANCE") "1%")
        (field (name "RESISTANCE") "330Ω")
        (field (name "POWER RATING") "0.1W")
      )
      (libsource (lib "Inverter_25kW") (part "RC0603FR-13330RL"))
    )
    (comp (ref "R162")
      (value "CRCW060320K0FKTA")
      (footprint "FP-MCR03-IPC_B")
      (description "RES SMD 20K OHM 1% 1/10W 0603")
      (fields
        (field (name "MANUFACTURER") "VISHAY DALE")
        (field (name "TOLERANCE") "1%")
        (field (name "RESISTANCE") "20kΩ")
        (field (name "POWER RATING") "0.1W")
      )
      (libsource (lib "Inverter_25kW") (part "CRCW060320K0FKTA"))
    )
    (comp (ref "R163")
      (value "ERJ3EKF1002V")
      (footprint "FP-MCR03-IPC_B")
      (description "RES SMD 10K OHM 1% 1/10W 0603")
      (fields
        (field (name "MANUFACTURER") "PANASONIC")
        (field (name "MANUFACTURER PART NUMBER") "ERJ-3EKF1002V")
        (field (name "RESISTANCE") "10kΩ")
        (field (name "MAX POWER DISSIPATION") "0.1W")
      )
      (libsource (lib "Inverter_25kW") (part "ERJ3EKF1002V"))
    )
    (comp (ref "R176")
      (value "RC0603FR-07100KL")
      (footprint "FP-MCR03-IPC_B")
      (description "RES 100K OHM 1% 1/10W 0603")
      (fields
        (field (name "MANUFACTURER") "YAGEO")
        (field (name "TOLERANCE") "1%")
        (field (name "RESISTANCE") "100kΩ")
        (field (name "POWER RATING") "0.1W")
      )
      (libsource (lib "Inverter_25kW") (part "RC0603FR-07100KL"))
    )
    (comp (ref "R177")
      (value "RC0603FR-07100KL")
      (footprint "FP-MCR03-IPC_B")
      (description "RES 100K OHM 1% 1/10W 0603")
      (fields
        (field (name "MANUFACTURER") "YAGEO")
        (field (name "TOLERANCE") "1%")
        (field (name "RESISTANCE") "100kΩ")
        (field (name "POWER RATING") "0.1W")
      )
      (libsource (lib "Inverter_25kW") (part "RC0603FR-07100KL"))
    )
    (comp (ref "R179")
      (value "RC0603FR-07100KL")
      (footprint "FP-MCR03-IPC_B")
      (description "RES 100K OHM 1% 1/10W 0603")
      (fields
        (field (name "MANUFACTURER") "YAGEO")
        (field (name "TOLERANCE") "1%")
        (field (name "RESISTANCE") "100kΩ")
        (field (name "POWER RATING") "0.1W")
      )
      (libsource (lib "Inverter_25kW") (part "RC0603FR-07100KL"))
    )
    (comp (ref "R180")
      (value "RC0603FR-07100KL")
      (footprint "FP-MCR03-IPC_B")
      (description "RES 100K OHM 1% 1/10W 0603")
      (fields
        (field (name "MANUFACTURER") "YAGEO")
        (field (name "TOLERANCE") "1%")
        (field (name "RESISTANCE") "100kΩ")
        (field (name "POWER RATING") "0.1W")
      )
      (libsource (lib "Inverter_25kW") (part "RC0603FR-07100KL"))
    )
    (comp (ref "R181")
      (value "ERJ-3EKF49R9V")
      (footprint "FP-MCR03-IPC_B")
      (description "RES SMD 49.9 OHM 1% 1/10W 0603")
      (fields
        (field (name "MANUFACTURER") "PANASONIC")
        (field (name "TOLERANCE") "1%")
        (field (name "RESISTANCE") "49.9Ω")
        (field (name "POWER RATING") "0.1W")
      )
      (libsource (lib "Inverter_25kW") (part "ERJ-3EKF49R9V"))
    )
    (comp (ref "R182")
      (value "ERJ-3EKF49R9V")
      (footprint "FP-MCR03-IPC_B")
      (description "RES SMD 49.9 OHM 1% 1/10W 0603")
      (fields
        (field (name "MANUFACTURER") "PANASONIC")
        (field (name "TOLERANCE") "1%")
        (field (name "RESISTANCE") "49.9Ω")
        (field (name "POWER RATING") "0.1W")
      )
      (libsource (lib "Inverter_25kW") (part "ERJ-3EKF49R9V"))
    )
    (comp (ref "R184")
      (value "RC0603FR-07100KL")
      (footprint "FP-MCR03-IPC_B")
      (description "RES 100K OHM 1% 1/10W 0603")
      (fields
        (field (name "MANUFACTURER") "YAGEO")
        (field (name "TOLERANCE") "1%")
        (field (name "RESISTANCE") "100kΩ")
        (field (name "POWER RATING") "0.1W")
      )
      (libsource (lib "Inverter_25kW") (part "RC0603FR-07100KL"))
    )
    (comp (ref "R186")
      (value "ERJ-3EKF49R9V")
      (footprint "FP-MCR03-IPC_B")
      (description "RES SMD 49.9 OHM 1% 1/10W 0603")
      (fields
        (field (name "MANUFACTURER") "PANASONIC")
        (field (name "TOLERANCE") "1%")
        (field (name "RESISTANCE") "49.9Ω")
        (field (name "POWER RATING") "0.1W")
      )
      (libsource (lib "Inverter_25kW") (part "ERJ-3EKF49R9V"))
    )
    (comp (ref "R187")
      (value "RC0603FR-07100KL")
      (footprint "FP-MCR03-IPC_B")
      (description "RES 100K OHM 1% 1/10W 0603")
      (fields
        (field (name "MANUFACTURER") "YAGEO")
        (field (name "TOLERANCE") "1%")
        (field (name "RESISTANCE") "100kΩ")
        (field (name "POWER RATING") "0.1W")
      )
      (libsource (lib "Inverter_25kW") (part "RC0603FR-07100KL"))
    )
    (comp (ref "R189")
      (value "ERJ3EKF1002V")
      (footprint "FP-MCR03-IPC_B")
      (description "RES SMD 10K OHM 1% 1/10W 0603")
      (fields
        (field (name "MANUFACTURER") "PANASONIC")
        (field (name "MANUFACTURER PART NUMBER") "ERJ-3EKF1002V")
        (field (name "RESISTANCE") "10kΩ")
        (field (name "MAX POWER DISSIPATION") "0.1W")
      )
      (libsource (lib "Inverter_25kW") (part "ERJ3EKF1002V"))
    )
    (comp (ref "R204")
      (value "ERJ-3EKF49R9V")
      (footprint "FP-MCR03-IPC_B")
      (description "RES SMD 49.9 OHM 1% 1/10W 0603")
      (fields
        (field (name "MANUFACTURER") "PANASONIC")
        (field (name "TOLERANCE") "1%")
        (field (name "RESISTANCE") "49.9Ω")
        (field (name "POWER RATING") "0.1W")
      )
      (libsource (lib "Inverter_25kW") (part "ERJ-3EKF49R9V"))
    )
    (comp (ref "R231")
      (value "ERJ3EKF1002V")
      (footprint "FP-MCR03-IPC_B")
      (description "RES SMD 10K OHM 1% 1/10W 0603")
      (fields
        (field (name "MANUFACTURER") "PANASONIC")
        (field (name "MANUFACTURER PART NUMBER") "ERJ-3EKF1002V")
        (field (name "RESISTANCE") "10kΩ")
        (field (name "MAX POWER DISSIPATION") "0.1W")
      )
      (libsource (lib "Inverter_25kW") (part "ERJ3EKF1002V"))
    )
    (comp (ref "R232")
      (value "ERJ3EKF1002V")
      (footprint "FP-MCR03-IPC_B")
      (description "RES SMD 10K OHM 1% 1/10W 0603")
      (fields
        (field (name "MANUFACTURER") "PANASONIC")
        (field (name "MANUFACTURER PART NUMBER") "ERJ-3EKF1002V")
        (field (name "RESISTANCE") "10kΩ")
        (field (name "MAX POWER DISSIPATION") "0.1W")
      )
      (libsource (lib "Inverter_25kW") (part "ERJ3EKF1002V"))
    )
    (comp (ref "R233")
      (value "ERJ3EKF1002V")
      (footprint "FP-MCR03-IPC_B")
      (description "RES SMD 10K OHM 1% 1/10W 0603")
      (fields
        (field (name "MANUFACTURER") "PANASONIC")
        (field (name "MANUFACTURER PART NUMBER") "ERJ-3EKF1002V")
        (field (name "RESISTANCE") "10kΩ")
        (field (name "MAX POWER DISSIPATION") "0.1W")
      )
      (libsource (lib "Inverter_25kW") (part "ERJ3EKF1002V"))
    )
    (comp (ref "R234")
      (value "ERJ3EKF1002V")
      (footprint "FP-MCR03-IPC_B")
      (description "RES SMD 10K OHM 1% 1/10W 0603")
      (fields
        (field (name "MANUFACTURER") "PANASONIC")
        (field (name "MANUFACTURER PART NUMBER") "ERJ-3EKF1002V")
        (field (name "RESISTANCE") "10kΩ")
        (field (name "MAX POWER DISSIPATION") "0.1W")
      )
      (libsource (lib "Inverter_25kW") (part "ERJ3EKF1002V"))
    )
    (comp (ref "R235")
      (value "ERJ3EKF1002V")
      (footprint "FP-MCR03-IPC_B")
      (description "RES SMD 10K OHM 1% 1/10W 0603")
      (fields
        (field (name "MANUFACTURER") "PANASONIC")
        (field (name "MANUFACTURER PART NUMBER") "ERJ-3EKF1002V")
        (field (name "RESISTANCE") "10kΩ")
        (field (name "MAX POWER DISSIPATION") "0.1W")
      )
      (libsource (lib "Inverter_25kW") (part "ERJ3EKF1002V"))
    )
    (comp (ref "R236")
      (value "ERJ3EKF1002V")
      (footprint "FP-MCR03-IPC_B")
      (description "RES SMD 10K OHM 1% 1/10W 0603")
      (fields
        (field (name "MANUFACTURER") "PANASONIC")
        (field (name "MANUFACTURER PART NUMBER") "ERJ-3EKF1002V")
        (field (name "RESISTANCE") "10kΩ")
        (field (name "MAX POWER DISSIPATION") "0.1W")
      )
      (libsource (lib "Inverter_25kW") (part "ERJ3EKF1002V"))
    )
    (comp (ref "U8")
      (value "ISO722MDR")
      (footprint "D0008B_L")
      (description "DGTL ISO 2500VRMS 1CH GP 8SOIC")
      (fields
        (field (name "MANUFACTURER PART NUMBER") "ISO722MDR")
        (field (name "MANUFACTURER") "TEXAS INSTRUMENTS")
      )
      (libsource (lib "Altium Content Vault") (part "TI-ISO722M-SOIC_D-8"))
    )
    (comp (ref "U9")
      (value "MCP6292-E/MS")
      (footprint "MSOP-MS8_L")
      (description "IC OPAMP GP 2 CIRCUIT 8MSOP")
      (fields (field (name "MANUFACTURER") "MICROCHIP") (field (name "MANUFACTURER PRINT") "MICROCHIP"))
      (libsource (lib "Inverter_25kW") (part "MCP6292-E/MS"))
    )
    (comp (ref "U10")
      (value "TS431IYLT")
      (footprint "SOT95P280X145-5N")
      (description "IC VREF SHUNT ADJ 2% SOT23-5")
      (fields
        (field (name "MANUFACTURER") "STMICROELECTRONICS")
        (field (name "TOLERANCE") "2%")
        (field (name "MANUFACTURER PRINT") "ST")
      )
      (libsource (lib "Inverter_25kW") (part "TS431IYLT"))
    )
    (comp (ref "U11")
      (value "LTC6992CS6-2#TRMPBF")
      (footprint "SOT95P280X100-6N")
      (description "IC OSC SILICON PROG TSOT23-6")
      (fields
        (field (name "MANUFACTURER") "ANALOG DEVICES")
        (field (name "MANUFACTURER PRINT") "ANALOG DEVICES")
      )
      (libsource (lib "Inverter_25kW") (part "LTC6992CS6-2#TRMPBF"))
    )
    (comp (ref "U13")
      (value "SN74LV541ATPWR")
      (footprint "PW0020A_L")
      (description "IC BUF NON-INVERT 5.5V 20TSSOP")
      (fields
        (field (name "GENERIC PART NUMBER") "SN74LV541AT")
        (field (name "MANUFACTURER") "TEXAS INSTRUMENTS")
        (field (name "MANUFACTURER PART NUMBER") "SN74LV541ATPWR")
      )
      (libsource (lib "Altium Content Vault") (part "TI-SN54_74_CD74XXXX541XX-20"))
    )
    (comp (ref "U14")
      (value "UCC5350SBD")
      (footprint "D0008B_HV")
      (description "5A/5A, 3-KVRMS SINGLE-CHANNEL IS")
      (fields
        (field (name "MANUFACTURER") "TEXAS INSTRUMENTS")
        (field (name "MANUFACTURER PRINT") "TEXAS INSTRUMENTS")
        (field (name "COPYRIGHT") "Copyright (C) 2021 Ultra Librarian. All rights reserved.")
      )
      (libsource (lib "Inverter_25kW") (part "UCC5350SBD"))
    )
    (comp (ref "U15")
      (value "UCC5350SBD")
      (footprint "D0008B_HV")
      (description "5A/5A, 3-KVRMS SINGLE-CHANNEL IS")
      (fields
        (field (name "MANUFACTURER") "TEXAS INSTRUMENTS")
        (field (name "MANUFACTURER PRINT") "TEXAS INSTRUMENTS")
        (field (name "COPYRIGHT") "Copyright (C) 2021 Ultra Librarian. All rights reserved.")
      )
      (libsource (lib "Inverter_25kW") (part "UCC5350SBD"))
    )
    (comp (ref "U16")
      (value "MGJ2D121503SC")
      (footprint "Inverter_25kW:MGJ2D121509SC")
      (description "DC DC CONVERTER 15V -3V 1.7W")
      (fields (field (name "MANUFACTURER") "MURATA") (field (name "MANUFACTURER PRINT") "MURATA"))
      (libsource (lib "Inverter_25kW") (part "MGJ2D121503SC"))
    )
    (comp (ref "U17")
      (value "MGJ2D121503SC")
      (footprint "Inverter_25kW:MGJ2D121509SC")
      (description "DC DC CONVERTER 15V -3V 1.7W")
      (fields (field (name "MANUFACTURER") "MURATA") (field (name "MANUFACTURER PRINT") "MURATA"))
      (libsource (lib "Inverter_25kW") (part "MGJ2D121503SC"))
    )
    (comp (ref "U20")
      (value "UCC5350SBD")
      (footprint "D0008B_HV")
      (description "5A/5A, 3-KVRMS SINGLE-CHANNEL IS")
      (fields
        (field (name "MANUFACTURER") "TEXAS INSTRUMENTS")
        (field (name "MANUFACTURER PRINT") "TEXAS INSTRUMENTS")
        (field (name "COPYRIGHT") "Copyright (C) 2021 Ultra Librarian. All rights reserved.")
      )
      (libsource (lib "Inverter_25kW") (part "UCC5350SBD"))
    )
    (comp (ref "U22")
      (value "UCC5350SBD")
      (footprint "D0008B_HV")
      (description "5A/5A, 3-KVRMS SINGLE-CHANNEL IS")
      (fields
        (field (name "MANUFACTURER") "TEXAS INSTRUMENTS")
        (field (name "MANUFACTURER PRINT") "TEXAS INSTRUMENTS")
        (field (name "COPYRIGHT") "Copyright (C) 2021 Ultra Librarian. All rights reserved.")
      )
      (libsource (lib "Inverter_25kW") (part "UCC5350SBD"))
    )
    (comp (ref "U24")
      (value "MGJ2D121503SC")
      (footprint "Inverter_25kW:MGJ2D121509SC")
      (description "DC DC CONVERTER 15V -3V 1.7W")
      (fields (field (name "MANUFACTURER") "MURATA") (field (name "MANUFACTURER PRINT") "MURATA"))
      (libsource (lib "Inverter_25kW") (part "MGJ2D121503SC"))
    )
    (comp (ref "U25")
      (value "MGJ2D121503SC")
      (footprint "Inverter_25kW:MGJ2D121509SC")
      (description "DC DC CONVERTER 15V -3V 1.7W")
      (fields (field (name "MANUFACTURER") "MURATA") (field (name "MANUFACTURER PRINT") "MURATA"))
      (libsource (lib "Inverter_25kW") (part "MGJ2D121503SC"))
    )
    (comp (ref "U26")
      (value "UCC5350SBD")
      (footprint "D0008B_HV")
      (description "5A/5A, 3-KVRMS SINGLE-CHANNEL IS")
      (fields
        (field (name "MANUFACTURER") "TEXAS INSTRUMENTS")
        (field (name "MANUFACTURER PRINT") "TEXAS INSTRUMENTS")
        (field (name "COPYRIGHT") "Copyright (C) 2021 Ultra Librarian. All rights reserved.")
      )
      (libsource (lib "Inverter_25kW") (part "UCC5350SBD"))
    )
    (comp (ref "U27")
      (value "UCC5350SBD")
      (footprint "D0008B_HV")
      (description "5A/5A, 3-KVRMS SINGLE-CHANNEL IS")
      (fields
        (field (name "MANUFACTURER") "TEXAS INSTRUMENTS")
        (field (name "MANUFACTURER PRINT") "TEXAS INSTRUMENTS")
        (field (name "COPYRIGHT") "Copyright (C) 2021 Ultra Librarian. All rights reserved.")
      )
      (libsource (lib "Inverter_25kW") (part "UCC5350SBD"))
    )
    (comp (ref "U28")
      (value "MGJ2D121503SC")
      (footprint "Inverter_25kW:MGJ2D121509SC")
      (description "DC DC CONVERTER 15V -3V 1.7W")
      (fields (field (name "MANUFACTURER") "MURATA") (field (name "MANUFACTURER PRINT") "MURATA"))
      (libsource (lib "Inverter_25kW") (part "MGJ2D121503SC"))
    )
    (comp (ref "U29")
      (value "MGJ2D121503SC")
      (footprint "Inverter_25kW:MGJ2D121509SC")
      (description "DC DC CONVERTER 15V -3V 1.7W")
      (fields (field (name "MANUFACTURER") "MURATA") (field (name "MANUFACTURER PRINT") "MURATA"))
      (libsource (lib "Inverter_25kW") (part "MGJ2D121503SC"))
    )
  )
  (nets
    (net (code "1") (name "+3.3V") (class "Default")
      (node (ref "C73") (pin "1") (pinfunction "1_1") (pintype "passive"))
      (node (ref "U8") (pin "8") (pinfunction "VCC2_8") (pintype "power_in"))
    )
    (net (code "2") (name "+5V") (class "Default")
      (node (ref "C117") (pin "1") (pinfunction "1_1") (pintype "passive"))
      (node (ref "C124") (pin "1") (pinfunction "1_1") (pintype "passive"))
      (node (ref "C140") (pin "1") (pinfunction "1_1") (pintype "passive"))
      (node (ref "C145") (pin "1") (pinfunction "1_1") (pintype "passive"))
      (node (ref "C88") (pin "1") (pinfunction "1_1") (pintype "passive"))
      (node (ref "C93") (pin "1") (pinfunction "1_1") (pintype "passive"))
      (node (ref "C95") (pin "1") (pinfunction "1_1") (pintype "passive"))
      (node (ref "U13") (pin "20") (pinfunction "VCC_20") (pintype "power_in"))
      (node (ref "U15") (pin "1") (pinfunction "VCC1_1") (pintype "power_in"))
      (node (ref "U22") (pin "1") (pinfunction "VCC1_1") (pintype "power_in"))
      (node (ref "U27") (pin "1") (pinfunction "VCC1_1") (pintype "power_in"))
    )
    (net (code "3") (name "+5V_ALT") (class "Default")
      (node (ref "C110") (pin "1") (pinfunction "1_1") (pintype "passive"))
      (node (ref "C118") (pin "1") (pinfunction "1_1") (pintype "passive"))
      (node (ref "C137") (pin "1") (pinfunction "1_1") (pintype "passive"))
      (node (ref "C141") (pin "1") (pinfunction "1_1") (pintype "passive"))
      (node (ref "C87") (pin "1") (pinfunction "1_1") (pintype "passive"))
      (node (ref "C89") (pin "1") (pinfunction "1_1") (pintype "passive"))
      (node (ref "U14") (pin "1") (pinfunction "VCC1_1") (pintype "power_in"))
      (node (ref "U20") (pin "1") (pinfunction "VCC1_1") (pintype "power_in"))
      (node (ref "U26") (pin "1") (pinfunction "VCC1_1") (pintype "power_in"))
    )
    (net (code "4") (name "+5V_NTC") (class "Default")
      (node (ref "C14") (pin "1") (pinfunction "1_1") (pintype "passive"))
      (node (ref "C74") (pin "1") (pinfunction "1_1") (pintype "passive"))
      (node (ref "C75") (pin "1") (pinfunction "1_1") (pintype "passive"))
      (node (ref "R158") (pin "2") (pinfunction "2_2") (pintype "passive"))
      (node (ref "R47") (pin "2") (pinfunction "2_2") (pintype "passive"))
      (node (ref "U11") (pin "5") (pinfunction "V+_5") (pintype "passive"))
      (node (ref "U8") (pin "1") (pinfunction "VCC1_1") (pintype "power_in"))
      (node (ref "U8") (pin "3") (pinfunction "VCC1_3") (pintype "power_in"))
      (node (ref "U9") (pin "8") (pinfunction "VDD_8") (pintype "power_in"))
    )
    (net (code "5") (name "+12V") (class "Default")
      (node (ref "L1") (pin "1") (pinfunction "1_1") (pintype "passive"))
      (node (ref "L2") (pin "1") (pinfunction "1_1") (pintype "passive"))
      (node (ref "L3") (pin "1") (pinfunction "1_1") (pintype "passive"))
      (node (ref "L4") (pin "1") (pinfunction "1_1") (pintype "passive"))
      (node (ref "L5") (pin "1") (pinfunction "1_1") (pintype "passive"))
      (node (ref "L6") (pin "1") (pinfunction "1_1") (pintype "passive"))
    )
    (net (code "6") (name "/+15V_U_HS") (class "Default")
      (node (ref "C122") (pin "1") (pinfunction "1_1") (pintype "passive"))
      (node (ref "C127") (pin "1") (pinfunction "1_1") (pintype "passive"))
      (node (ref "U20") (pin "5") (pinfunction "VCC2_5") (pintype "power_in"))
      (node (ref "U24") (pin "7") (pinfunction "+VOUT_7") (pintype "passive"))
    )
    (net (code "7") (name "/+15V_U_LS") (class "Default")
      (node (ref "C143") (pin "1") (pinfunction "1_1") (pintype "passive"))
      (node (ref "C146") (pin "1") (pinfunction "1_1") (pintype "passive"))
      (node (ref "U26") (pin "5") (pinfunction "VCC2_5") (pintype "power_in"))
      (node (ref "U28") (pin "7") (pinfunction "+VOUT_7") (pintype "passive"))
    )
    (net (code "8") (name "/+15V_V_HS") (class "Default")
      (node (ref "C91") (pin "1") (pinfunction "1_1") (pintype "passive"))
      (node (ref "C96") (pin "1") (pinfunction "1_1") (pintype "passive"))
      (node (ref "U14") (pin "5") (pinfunction "VCC2_5") (pintype "power_in"))
      (node (ref "U16") (pin "7") (pinfunction "+VOUT_7") (pintype "passive"))
    )
    (net (code "9") (name "/+15V_V_LS") (class "Default")
      (node (ref "C151") (pin "1") (pinfunction "1_1") (pintype "passive"))
      (node (ref "C153") (pin "1") (pinfunction "1_1") (pintype "passive"))
      (node (ref "U27") (pin "5") (pinfunction "VCC2_5") (pintype "power_in"))
      (node (ref "U29") (pin "7") (pinfunction "+VOUT_7") (pintype "passive"))
    )
    (net (code "10") (name "/+15V_W_HS") (class "Default")
      (node (ref "C101") (pin "1") (pinfunction "1_1") (pintype "passive"))
      (node (ref "C99") (pin "1") (pinfunction "1_1") (pintype "passive"))
      (node (ref "U15") (pin "5") (pinfunction "VCC2_5") (pintype "power_in"))
      (node (ref "U17") (pin "7") (pinfunction "+VOUT_7") (pintype "passive"))
    )
    (net (code "11") (name "/+15V_W_LS") (class "Default")
      (node (ref "C131") (pin "1") (pinfunction "1_1") (pintype "passive"))
      (node (ref "C134") (pin "1") (pinfunction "1_1") (pintype "passive"))
      (node (ref "U22") (pin "5") (pinfunction "VCC2_5") (pintype "power_in"))
      (node (ref "U25") (pin "7") (pinfunction "+VOUT_7") (pintype "passive"))
    )
    (net (code "12") (name "/-3V_U_HS") (class "Default")
      (node (ref "C123") (pin "2") (pinfunction "2_2") (pintype "passive"))
      (node (ref "C128") (pin "2") (pinfunction "2_2") (pintype "passive"))
      (node (ref "U20") (pin "8") (pinfunction "VEE2_8") (pintype "power_in"))
      (node (ref "U24") (pin "5") (pinfunction "-VOUT_5") (pintype "passive"))
    )
    (net (code "13") (name "/-3V_U_LS") (class "Default")
      (node (ref "C144") (pin "2") (pinfunction "2_2") (pintype "passive"))
      (node (ref "C147") (pin "2") (pinfunction "2_2") (pintype "passive"))
      (node (ref "U26") (pin "8") (pinfunction "VEE2_8") (pintype "power_in"))
      (node (ref "U28") (pin "5") (pinfunction "-VOUT_5") (pintype "passive"))
    )
    (net (code "14") (name "/-3V_V_HS") (class "Default")
      (node (ref "C92") (pin "2") (pinfunction "2_2") (pintype "passive"))
      (node (ref "C97") (pin "2") (pinfunction "2_2") (pintype "passive"))
      (node (ref "U14") (pin "8") (pinfunction "VEE2_8") (pintype "power_in"))
      (node (ref "U16") (pin "5") (pinfunction "-VOUT_5") (pintype "passive"))
    )
    (net (code "15") (name "/-3V_V_LS") (class "Default")
      (node (ref "C150") (pin "2") (pinfunction "2_2") (pintype "passive"))
      (node (ref "C152") (pin "2") (pinfunction "2_2") (pintype "passive"))
      (node (ref "U27") (pin "8") (pinfunction "VEE2_8") (pintype "power_in"))
      (node (ref "U29") (pin "5") (pinfunction "-VOUT_5") (pintype "passive"))
    )
    (net (code "16") (name "/-3V_W_HS") (class "Default")
      (node (ref "C100") (pin "2") (pinfunction "2_2") (pintype "passive"))
      (node (ref "C98") (pin "2") (pinfunction "2_2") (pintype "passive"))
      (node (ref "U15") (pin "8") (pinfunction "VEE2_8") (pintype "power_in"))
      (node (ref "U17") (pin "5") (pinfunction "-VOUT_5") (pintype "passive"))
    )
    (net (code "17") (name "/-3V_W_LS") (class "Default")
      (node (ref "C130") (pin "2") (pinfunction "2_2") (pintype "passive"))
      (node (ref "C133") (pin "2") (pinfunction "2_2") (pintype "passive"))
      (node (ref "U22") (pin "8") (pinfunction "VEE2_8") (pintype "power_in"))
      (node (ref "U25") (pin "5") (pinfunction "-VOUT_5") (pintype "passive"))
    )
    (net (code "18") (name "/G1H") (class "Default")
      (node (ref "R82") (pin "1") (pinfunction "1_1") (pintype "passive"))
      (node (ref "U20") (pin "6") (pinfunction "OUTH_6") (pintype "output"))
    )
    (net (code "19") (name "/G1L") (class "Default")
      (node (ref "R75") (pin "1") (pinfunction "1_1") (pintype "passive"))
      (node (ref "U20") (pin "7") (pinfunction "OUTL_7") (pintype "input"))
    )
    (net (code "20") (name "/G2H") (class "Default")
      (node (ref "R89") (pin "1") (pinfunction "1_1") (pintype "passive"))
      (node (ref "U26") (pin "6") (pinfunction "OUTH_6") (pintype "output"))
    )
    (net (code "21") (name "/G2L") (class "Default")
      (node (ref "R95") (pin "1") (pinfunction "1_1") (pintype "passive"))
      (node (ref "U26") (pin "7") (pinfunction "OUTL_7") (pintype "input"))
    )
    (net (code "22") (name "/G3H") (class "Default")
      (node (ref "R63") (pin "1") (pinfunction "1_1") (pintype "passive"))
      (node (ref "U14") (pin "6") (pinfunction "OUTH_6") (pintype "output"))
    )
    (net (code "23") (name "/G3L") (class "Default")
      (node (ref "R61") (pin "1") (pinfunction "1_1") (pintype "passive"))
      (node (ref "U14") (pin "7") (pinfunction "OUTL_7") (pintype "input"))
    )
    (net (code "24") (name "/G4H") (class "Default")
      (node (ref "R88") (pin "1") (pinfunction "1_1") (pintype "passive"))
      (node (ref "U27") (pin "6") (pinfunction "OUTH_6") (pintype "output"))
    )
    (net (code "25") (name "/G4L") (class "Default")
      (node (ref "R96") (pin "1") (pinfunction "1_1") (pintype "passive"))
      (node (ref "U27") (pin "7") (pinfunction "OUTL_7") (pintype "input"))
    )
    (net (code "26") (name "/G5H") (class "Default")
      (node (ref "R60") (pin "1") (pinfunction "1_1") (pintype "passive"))
      (node (ref "U15") (pin "6") (pinfunction "OUTH_6") (pintype "output"))
    )
    (net (code "27") (name "/G5L") (class "Default")
      (node (ref "R64") (pin "1") (pinfunction "1_1") (pintype "passive"))
      (node (ref "U15") (pin "7") (pinfunction "OUTL_7") (pintype "input"))
    )
    (net (code "28") (name "/G6H") (class "Default")
      (node (ref "R74") (pin "1") (pinfunction "1_1") (pintype "passive"))
      (node (ref "U22") (pin "6") (pinfunction "OUTH_6") (pintype "output"))
    )
    (net (code "29") (name "/G6L") (class "Default")
      (node (ref "R83") (pin "1") (pinfunction "1_1") (pintype "passive"))
      (node (ref "U22") (pin "7") (pinfunction "OUTL_7") (pintype "input"))
    )
    (net (code "30") (name "/GD_DIS_FILT") (class "Default")
      (node (ref "C94") (pin "1") (pinfunction "1_1") (pintype "passive"))
      (node (ref "R189") (pin "2") (pinfunction "2_2") (pintype "passive"))
      (node (ref "R65") (pin "2") (pinfunction "2_2") (pintype "passive"))
      (node (ref "U13") (pin "1") (pinfunction "~{OE1}_1") (pintype "input"))
      (node (ref "U13") (pin "19") (pinfunction "~{OE2}_19") (pintype "input"))
    )
    (net (code "31") (name "/MOD") (class "Default")
      (node (ref "C76") (pin "1") (pinfunction "1_1") (pintype "passive"))
      (node (ref "R52") (pin "1") (pinfunction "1_1") (pintype "passive"))
      (node (ref "U11") (pin "1") (pinfunction "MOD_1") (pintype "passive"))
    )
    (net (code "32") (name "/NTC_BIAS") (class "Default")
      (node (ref "C13") (pin "1") (pinfunction "1_1") (pintype "passive"))
      (node (ref "R48") (pin "1") (pinfunction "1_1") (pintype "passive"))
      (node (ref "R49") (pin "2") (pinfunction "2_2") (pintype "passive"))
      (node (ref "U9") (pin "3") (pinfunction "VINA+_3") (pintype "input"))
    )
    (net (code "33") (name "/NTC_PWM") (class "Default")
      (node (ref "U11") (pin "6") (pinfunction "OUT_6") (pintype "passive"))
      (node (ref "U8") (pin "2") (pinfunction "IN_2") (pintype "input"))
    )
    (net (code "34") (name "/U_HS") (class "Default")
      (node (ref "R176") (pin "2") (pinfunction "2_2") (pintype "passive"))
      (node (ref "R204") (pin "1") (pinfunction "1_1") (pintype "passive"))
      (node (ref "R77") (pin "1") (pinfunction "1_1") (pintype "passive"))
      (node (ref "U13") (pin "14") (pinfunction "Y5_14") (pintype "tri_state"))
    )
    (net (code "35") (name "/U_HS+_FILT") (class "Default")
      (node (ref "C115") (pin "1") (pinfunction "1_1") (pintype "passive"))
      (node (ref "R77") (pin "2") (pinfunction "2_2") (pintype "passive"))
      (node (ref "U20") (pin "2") (pinfunction "IN+_2") (pintype "input"))
    )
    (net (code "36") (name "/U_HS-_FILT") (class "Default")
      (node (ref "C36") (pin "1") (pinfunction "1_1") (pintype "passive"))
      (node (ref "R204") (pin "2") (pinfunction "2_2") (pintype "passive"))
      (node (ref "U26") (pin "3") (pinfunction "IN-_3") (pintype "input"))
    )
    (net (code "37") (name "/U_LS") (class "Default")
      (node (ref "R179") (pin "2") (pinfunction "2_2") (pintype "passive"))
      (node (ref "R80") (pin "1") (pinfunction "1_1") (pintype "passive"))
      (node (ref "R91") (pin "1") (pinfunction "1_1") (pintype "passive"))
      (node (ref "U13") (pin "15") (pinfunction "Y4_15") (pintype "tri_state"))
    )
    (net (code "38") (name "/U_LS+_FILT") (class "Default")
      (node (ref "C138") (pin "1") (pinfunction "1_1") (pintype "passive"))
      (node (ref "R91") (pin "2") (pinfunction "2_2") (pintype "passive"))
      (node (ref "U26") (pin "2") (pinfunction "IN+_2") (pintype "input"))
    )
    (net (code "39") (name "/U_LS-_FILT") (class "Default")
      (node (ref "C120") (pin "1") (pinfunction "1_1") (pintype "passive"))
      (node (ref "R80") (pin "2") (pinfunction "2_2") (pintype "passive"))
      (node (ref "U20") (pin "3") (pinfunction "IN-_3") (pintype "input"))
    )
    (net (code "40") (name "/V_HS") (class "Default")
      (node (ref "R181") (pin "1") (pinfunction "1_1") (pintype "passive"))
      (node (ref "R184") (pin "2") (pinfunction "2_2") (pintype "passive"))
      (node (ref "R92") (pin "1") (pinfunction "1_1") (pintype "passive"))
      (node (ref "U13") (pin "17") (pinfunction "Y2_17") (pintype "tri_state"))
    )
    (net (code "41") (name "/V_HS+_FILT") (class "Default")
      (node (ref "C24") (pin "1") (pinfunction "1_1") (pintype "passive"))
      (node (ref "R181") (pin "2") (pinfunction "2_2") (pintype "passive"))
      (node (ref "U14") (pin "2") (pinfunction "IN+_2") (pintype "input"))
    )
    (net (code "42") (name "/V_HS-_FILT") (class "Default")
      (node (ref "C139") (pin "1") (pinfunction "1_1") (pintype "passive"))
      (node (ref "R92") (pin "2") (pinfunction "2_2") (pintype "passive"))
      (node (ref "U27") (pin "3") (pinfunction "IN-_3") (pintype "input"))
    )
    (net (code "43") (name "/V_LS") (class "Default")
      (node (ref "R186") (pin "1") (pinfunction "1_1") (pintype "passive"))
      (node (ref "R187") (pin "2") (pinfunction "2_2") (pintype "passive"))
      (node (ref "R94") (pin "1") (pinfunction "1_1") (pintype "passive"))
      (node (ref "U13") (pin "18") (pinfunction "Y1_18") (pintype "tri_state"))
    )
    (net (code "44") (name "/V_LS+_FILT") (class "Default")
      (node (ref "C142") (pin "1") (pinfunction "1_1") (pintype "passive"))
      (node (ref "R94") (pin "2") (pinfunction "2_2") (pintype "passive"))
      (node (ref "U27") (pin "2") (pinfunction "IN+_2") (pintype "input"))
    )
    (net (code "45") (name "/V_LS-_FILT") (class "Default")
      (node (ref "C26") (pin "1") (pinfunction "1_1") (pintype "passive"))
      (node (ref "R186") (pin "2") (pinfunction "2_2") (pintype "passive"))
      (node (ref "U14") (pin "3") (pinfunction "IN-_3") (pintype "input"))
    )
    (net (code "46") (name "/W_HS") (class "Default")
      (node (ref "R177") (pin "2") (pinfunction "2_2") (pintype "passive"))
      (node (ref "R62") (pin "1") (pinfunction "1_1") (pintype "passive"))
      (node (ref "R78") (pin "1") (pinfunction "1_1") (pintype "passive"))
      (node (ref "U13") (pin "11") (pinfunction "Y8_11") (pintype "tri_state"))
    )
    (net (code "47") (name "/W_HS+_FILT") (class "Default")
      (node (ref "C90") (pin "1") (pinfunction "1_1") (pintype "passive"))
      (node (ref "R62") (pin "2") (pinfunction "2_2") (pintype "passive"))
      (node (ref "U15") (pin "2") (pinfunction "IN+_2") (pintype "input"))
    )
    (net (code "48") (name "/W_HS-_FILT") (class "Default")
      (node (ref "C116") (pin "1") (pinfunction "1_1") (pintype "passive"))
      (node (ref "R78") (pin "2") (pinfunction "2_2") (pintype "passive"))
      (node (ref "U22") (pin "3") (pinfunction "IN-_3") (pintype "input"))
    )
    (net (code "49") (name "/W_LS") (class "Default")
      (node (ref "R180") (pin "2") (pinfunction "2_2") (pintype "passive"))
      (node (ref "R182") (pin "1") (pinfunction "1_1") (pintype "passive"))
      (node (ref "R81") (pin "1") (pinfunction "1_1") (pintype "passive"))
      (node (ref "U13") (pin "12") (pinfunction "Y7_12") (pintype "tri_state"))
    )
    (net (code "50") (name "/W_LS+_FILT") (class "Default")
      (node (ref "C121") (pin "1") (pinfunction "1_1") (pintype "passive"))
      (node (ref "R81") (pin "2") (pinfunction "2_2") (pintype "passive"))
      (node (ref "U22") (pin "2") (pinfunction "IN+_2") (pintype "input"))
    )
    (net (code "51") (name "/W_LS-_FILT") (class "Default")
      (node (ref "C25") (pin "1") (pinfunction "1_1") (pintype "passive"))
      (node (ref "R182") (pin "2") (pinfunction "2_2") (pintype "passive"))
      (node (ref "U15") (pin "3") (pinfunction "IN-_3") (pintype "input"))
    )
    (net (code "52") (name "G1") (class "Default")
      (node (ref "R231") (pin "2") (pinfunction "2_2") (pintype "passive"))
      (node (ref "R75") (pin "2") (pinfunction "2_2") (pintype "passive"))
      (node (ref "R82") (pin "2") (pinfunction "2_2") (pintype "passive"))
    )
    (net (code "53") (name "G2") (class "Default")
      (node (ref "R234") (pin "2") (pinfunction "2_2") (pintype "passive"))
      (node (ref "R89") (pin "2") (pinfunction "2_2") (pintype "passive"))
      (node (ref "R95") (pin "2") (pinfunction "2_2") (pintype "passive"))
    )
    (net (code "54") (name "G3") (class "Default")
      (node (ref "R232") (pin "2") (pinfunction "2_2") (pintype "passive"))
      (node (ref "R61") (pin "2") (pinfunction "2_2") (pintype "passive"))
      (node (ref "R63") (pin "2") (pinfunction "2_2") (pintype "passive"))
    )
    (net (code "55") (name "G4") (class "Default")
      (node (ref "R235") (pin "2") (pinfunction "2_2") (pintype "passive"))
      (node (ref "R88") (pin "2") (pinfunction "2_2") (pintype "passive"))
      (node (ref "R96") (pin "2") (pinfunction "2_2") (pintype "passive"))
    )
    (net (code "56") (name "G5") (class "Default")
      (node (ref "R233") (pin "2") (pinfunction "2_2") (pintype "passive"))
      (node (ref "R60") (pin "2") (pinfunction "2_2") (pintype "passive"))
      (node (ref "R64") (pin "2") (pinfunction "2_2") (pintype "passive"))
    )
    (net (code "57") (name "G6") (class "Default")
      (node (ref "R236") (pin "2") (pinfunction "2_2") (pintype "passive"))
      (node (ref "R74") (pin "2") (pinfunction "2_2") (pintype "passive"))
      (node (ref "R83") (pin "2") (pinfunction "2_2") (pintype "passive"))
    )
    (net (code "58") (name "GD_DIS") (class "Default")
      (node (ref "R65") (pin "1") (pinfunction "1_1") (pintype "passive"))
    )
    (net (code "59") (name "GND") (class "Default")
      (node (ref "C110") (pin "2") (pinfunction "2_2") (pintype "passive"))
      (node (ref "C115") (pin "2") (pinfunction "2_2") (pintype "passive"))
      (node (ref "C116") (pin "2") (pinfunction "2_2") (pintype "passive"))
      (node (ref "C117") (pin "2") (pinfunction "2_2") (pintype "passive"))
      (node (ref "C118") (pin "2") (pinfunction "2_2") (pintype "passive"))
      (node (ref "C120") (pin "2") (pinfunction "2_2") (pintype "passive"))
      (node (ref "C121") (pin "2") (pinfunction "2_2") (pintype "passive"))
      (node (ref "C124") (pin "2") (pinfunction "2_2") (pintype "passive"))
      (node (ref "C137") (pin "2") (pinfunction "2_2") (pintype "passive"))
      (node (ref "C138") (pin "2") (pinfunction "2_2") (pintype "passive"))
      (node (ref "C139") (pin "2") (pinfunction "2_2") (pintype "passive"))
      (node (ref "C140") (pin "2") (pinfunction "2_2") (pintype "passive"))
      (node (ref "C141") (pin "2") (pinfunction "2_2") (pintype "passive"))
      (node (ref "C142") (pin "2") (pinfunction "2_2") (pintype "passive"))
      (node (ref "C145") (pin "2") (pinfunction "2_2") (pintype "passive"))
      (node (ref "C24") (pin "2") (pinfunction "2_2") (pintype "passive"))
      (node (ref "C25") (pin "2") (pinfunction "2_2") (pintype "passive"))
      (node (ref "C26") (pin "2") (pinfunction "2_2") (pintype "passive"))
      (node (ref "C36") (pin "2") (pinfunction "2_2") (pintype "passive"))
      (node (ref "C73") (pin "2") (pinfunction "2_2") (pintype "passive"))
      (node (ref "C87") (pin "2") (pinfunction "2_2") (pintype "passive"))
      (node (ref "C88") (pin "2") (pinfunction "2_2") (pintype "passive"))
      (node (ref "C89") (pin "2") (pinfunction "2_2") (pintype "passive"))
      (node (ref "C90") (pin "2") (pinfunction "2_2") (pintype "passive"))
      (node (ref "C93") (pin "2") (pinfunction "2_2") (pintype "passive"))
      (node (ref "C94") (pin "2") (pinfunction "2_2") (pintype "passive"))
      (node (ref "C95") (pin "2") (pinfunction "2_2") (pintype "passive"))
      (node (ref "L1") (pin "2") (pinfunction "2_2") (pintype "passive"))
      (node (ref "L2") (pin "2") (pinfunction "2_2") (pintype "passive"))
      (node (ref "L3") (pin "2") (pinfunction "2_2") (pintype "passive"))
      (node (ref "L4") (pin "2") (pinfunction "2_2") (pintype "passive"))
      (node (ref "L5") (pin "2") (pinfunction "2_2") (pintype "passive"))
      (node (ref "L6") (pin "2") (pinfunction "2_2") (pintype "passive"))
      (node (ref "R176") (pin "1") (pinfunction "1_1") (pintype "passive"))
      (node (ref "R177") (pin "1") (pinfunction "1_1") (pintype "passive"))
      (node (ref "R179") (pin "1") (pinfunction "1_1") (pintype "passive"))
      (node (ref "R180") (pin "1") (pinfunction "1_1") (pintype "passive"))
      (node (ref "R184") (pin "1") (pinfunction "1_1") (pintype "passive"))
      (node (ref "R187") (pin "1") (pinfunction "1_1") (pintype "passive"))
      (node (ref "R189") (pin "1") (pinfunction "1_1") (pintype "passive"))
      (node (ref "U13") (pin "10") (pinfunction "GND_10") (pintype "power_in"))
      (node (ref "U13") (pin "4") (pinfunction "A3_4") (pintype "input"))
      (node (ref "U13") (pin "7") (pinfunction "A6_7") (pintype "input"))
      (node (ref "U14") (pin "4") (pinfunction "GND1_4") (pintype "power_in"))
      (node (ref "U15") (pin "4") (pinfunction "GND1_4") (pintype "power_in"))
      (node (ref "U20") (pin "4") (pinfunction "GND1_4") (pintype "power_in"))
      (node (ref "U22") (pin "4") (pinfunction "GND1_4") (pintype "power_in"))
      (node (ref "U26") (pin "4") (pinfunction "GND1_4") (pintype "power_in"))
      (node (ref "U27") (pin "4") (pinfunction "GND1_4") (pintype "power_in"))
      (node (ref "U8") (pin "5") (pinfunction "GND2_5") (pintype "power_in"))
      (node (ref "U8") (pin "7") (pinfunction "~{EN}_7") (pintype "input"))
    )
    (net (code "60") (name "GND_NTC") (class "Default")
      (node (ref "C13") (pin "2") (pinfunction "2_2") (pintype "passive"))
      (node (ref "C14") (pin "2") (pinfunction "2_2") (pintype "passive"))
      (node (ref "C74") (pin "2") (pinfunction "2_2") (pintype "passive"))
      (node (ref "C75") (pin "2") (pinfunction "2_2") (pintype "passive"))
      (node (ref "C76") (pin "2") (pinfunction "2_2") (pintype "passive"))
      (node (ref "R157") (pin "1") (pinfunction "1_1") (pintype "passive"))
      (node (ref "R159") (pin "1") (pinfunction "1_1") (pintype "passive"))
      (node (ref "R163") (pin "1") (pinfunction "1_1") (pintype "passive"))
      (node (ref "R49") (pin "1") (pinfunction "1_1") (pintype "passive"))
      (node (ref "R50") (pin "1") (pinfunction "1_1") (pintype "passive"))
      (node (ref "U10") (pin "5") (pinfunction "5_5") (pintype "passive"))
      (node (ref "U11") (pin "2") (pinfunction "GND_2") (pintype "passive"))
      (node (ref "U8") (pin "4") (pinfunction "GND1_4") (pintype "power_in"))
      (node (ref "U9") (pin "4") (pinfunction "VSS_4") (pintype "power_in"))
    )
    (net (code "61") (name "NTC1") (class "Default")
      (node (ref "R160") (pin "2") (pinfunction "2_2") (pintype "passive"))
      (node (ref "R161") (pin "1") (pinfunction "1_1") (pintype "passive"))
    )
    (net (code "62") (name "NTC_ISO") (class "Default")
      (node (ref "U8") (pin "6") (pinfunction "OUT_6") (pintype "tri_state"))
    )
    (net (code "63") (name "Net-(R162-Pad1)") (class "Default")
      (node (ref "R162") (pin "1") (pinfunction "1_1") (pintype "passive"))
      (node (ref "R163") (pin "2") (pinfunction "2_2") (pintype "passive"))
      (node (ref "U10") (pin "4") (pinfunction "4_4") (pintype "passive"))
    )
    (net (code "64") (name "Net-(R162-Pad2)") (class "Default")
      (node (ref "R162") (pin "2") (pinfunction "2_2") (pintype "passive"))
      (node (ref "R47") (pin "1") (pinfunction "1_1") (pintype "passive"))
      (node (ref "R48") (pin "2") (pinfunction "2_2") (pintype "passive"))
      (node (ref "U10") (pin "3") (pinfunction "3_3") (pintype "passive"))
    )
    (net (code "65") (name "Net-(U9A-VINA-)") (class "Default")
      (node (ref "R161") (pin "2") (pinfunction "2_2") (pintype "passive"))
      (node (ref "U9") (pin "1") (pinfunction "VOUTA_1") (pintype "output"))
      (node (ref "U9") (pin "2") (pinfunction "VINA-_2") (pintype "input"))
    )
    (net (code "66") (name "Net-(U9B-VINB+)") (class "Default")
      (node (ref "R160") (pin "1") (pinfunction "1_1") (pintype "passive"))
      (node (ref "U9") (pin "5") (pinfunction "VINB+_5") (pintype "input"))
    )
    (net (code "67") (name "Net-(U9B-VINB-)") (class "Default")
      (node (ref "R50") (pin "2") (pinfunction "2_2") (pintype "passive"))
      (node (ref "R51") (pin "1") (pinfunction "1_1") (pintype "passive"))
      (node (ref "U9") (pin "6") (pinfunction "VINB-_6") (pintype "input"))
    )
    (net (code "68") (name "Net-(U9B-VOUTB)") (class "Default")
      (node (ref "R51") (pin "2") (pinfunction "2_2") (pintype "passive"))
      (node (ref "R52") (pin "2") (pinfunction "2_2") (pintype "passive"))
      (node (ref "U9") (pin "7") (pinfunction "VOUTB_7") (pintype "output"))
    )
    (net (code "69") (name "Net-(U11-DIV)") (class "Default")
      (node (ref "R157") (pin "2") (pinfunction "2_2") (pintype "passive"))
      (node (ref "R158") (pin "1") (pinfunction "1_1") (pintype "passive"))
      (node (ref "U11") (pin "4") (pinfunction "DIV_4") (pintype "passive"))
    )
    (net (code "70") (name "Net-(U11-SET)") (class "Default")
      (node (ref "R159") (pin "2") (pinfunction "2_2") (pintype "passive"))
      (node (ref "U11") (pin "3") (pinfunction "SET_3") (pintype "passive"))
    )
    (net (code "71") (name "Net-(U16-+VIN)") (class "Default")
      (node (ref "C106") (pin "1") (pinfunction "1_1") (pintype "passive"))
      (node (ref "L1") (pin "4") (pinfunction "4_4") (pintype "passive"))
      (node (ref "U16") (pin "1") (pinfunction "+VIN_1") (pintype "passive"))
    )
    (net (code "72") (name "Net-(U16--VIN)") (class "Default")
      (node (ref "C106") (pin "2") (pinfunction "2_2") (pintype "passive"))
      (node (ref "L1") (pin "3") (pinfunction "3_3") (pintype "passive"))
      (node (ref "U16") (pin "2") (pinfunction "-VIN_2") (pintype "passive"))
    )
    (net (code "73") (name "Net-(U17-+VIN)") (class "Default")
      (node (ref "C105") (pin "1") (pinfunction "1_1") (pintype "passive"))
      (node (ref "L2") (pin "4") (pinfunction "4_4") (pintype "passive"))
      (node (ref "U17") (pin "1") (pinfunction "+VIN_1") (pintype "passive"))
    )
    (net (code "74") (name "Net-(U17--VIN)") (class "Default")
      (node (ref "C105") (pin "2") (pinfunction "2_2") (pintype "passive"))
      (node (ref "L2") (pin "3") (pinfunction "3_3") (pintype "passive"))
      (node (ref "U17") (pin "2") (pinfunction "-VIN_2") (pintype "passive"))
    )
    (net (code "75") (name "Net-(U24-+VIN)") (class "Default")
      (node (ref "C136") (pin "1") (pinfunction "1_1") (pintype "passive"))
      (node (ref "L3") (pin "4") (pinfunction "4_4") (pintype "passive"))
      (node (ref "U24") (pin "1") (pinfunction "+VIN_1") (pintype "passive"))
    )
    (net (code "76") (name "Net-(U24--VIN)") (class "Default")
      (node (ref "C136") (pin "2") (pinfunction "2_2") (pintype "passive"))
      (node (ref "L3") (pin "3") (pinfunction "3_3") (pintype "passive"))
      (node (ref "U24") (pin "2") (pinfunction "-VIN_2") (pintype "passive"))
    )
    (net (code "77") (name "Net-(U25-+VIN)") (class "Default")
      (node (ref "C135") (pin "1") (pinfunction "1_1") (pintype "passive"))
      (node (ref "L4") (pin "4") (pinfunction "4_4") (pintype "passive"))
      (node (ref "U25") (pin "1") (pinfunction "+VIN_1") (pintype "passive"))
    )
    (net (code "78") (name "Net-(U25--VIN)") (class "Default")
      (node (ref "C135") (pin "2") (pinfunction "2_2") (pintype "passive"))
      (node (ref "L4") (pin "3") (pinfunction "3_3") (pintype "passive"))
      (node (ref "U25") (pin "2") (pinfunction "-VIN_2") (pintype "passive"))
    )
    (net (code "79") (name "Net-(U28-+VIN)") (class "Default")
      (node (ref "C157") (pin "1") (pinfunction "1_1") (pintype "passive"))
      (node (ref "L5") (pin "4") (pinfunction "4_4") (pintype "passive"))
      (node (ref "U28") (pin "1") (pinfunction "+VIN_1") (pintype "passive"))
    )
    (net (code "80") (name "Net-(U28--VIN)") (class "Default")
      (node (ref "C157") (pin "2") (pinfunction "2_2") (pintype "passive"))
      (node (ref "L5") (pin "3") (pinfunction "3_3") (pintype "passive"))
      (node (ref "U28") (pin "2") (pinfunction "-VIN_2") (pintype "passive"))
    )
    (net (code "81") (name "Net-(U29-+VIN)") (class "Default")
      (node (ref "C156") (pin "1") (pinfunction "1_1") (pintype "passive"))
      (node (ref "L6") (pin "4") (pinfunction "4_4") (pintype "passive"))
      (node (ref "U29") (pin "1") (pinfunction "+VIN_1") (pintype "passive"))
    )
    (net (code "82") (name "Net-(U29--VIN)") (class "Default")
      (node (ref "C156") (pin "2") (pinfunction "2_2") (pintype "passive"))
      (node (ref "L6") (pin "3") (pinfunction "3_3") (pintype "passive"))
      (node (ref "U29") (pin "2") (pinfunction "-VIN_2") (pintype "passive"))
    )
    (net (code "83") (name "S1") (class "Default")
      (node (ref "C122") (pin "2") (pinfunction "2_2") (pintype "passive"))
      (node (ref "C123") (pin "1") (pinfunction "1_1") (pintype "passive"))
      (node (ref "C127") (pin "2") (pinfunction "2_2") (pintype "passive"))
      (node (ref "C128") (pin "1") (pinfunction "1_1") (pintype "passive"))
      (node (ref "R231") (pin "1") (pinfunction "1_1") (pintype "passive"))
      (node (ref "U24") (pin "6") (pinfunction "0V_6") (pintype "passive"))
    )
    (net (code "84") (name "S2") (class "Default")
      (node (ref "C143") (pin "2") (pinfunction "2_2") (pintype "passive"))
      (node (ref "C144") (pin "1") (pinfunction "1_1") (pintype "passive"))
      (node (ref "C146") (pin "2") (pinfunction "2_2") (pintype "passive"))
      (node (ref "C147") (pin "1") (pinfunction "1_1") (pintype "passive"))
      (node (ref "R234") (pin "1") (pinfunction "1_1") (pintype "passive"))
      (node (ref "U28") (pin "6") (pinfunction "0V_6") (pintype "passive"))
    )
    (net (code "85") (name "S3") (class "Default")
      (node (ref "C91") (pin "2") (pinfunction "2_2") (pintype "passive"))
      (node (ref "C92") (pin "1") (pinfunction "1_1") (pintype "passive"))
      (node (ref "C96") (pin "2") (pinfunction "2_2") (pintype "passive"))
      (node (ref "C97") (pin "1") (pinfunction "1_1") (pintype "passive"))
      (node (ref "R232") (pin "1") (pinfunction "1_1") (pintype "passive"))
      (node (ref "U16") (pin "6") (pinfunction "0V_6") (pintype "passive"))
    )
    (net (code "86") (name "S4") (class "Default")
      (node (ref "C150") (pin "1") (pinfunction "1_1") (pintype "passive"))
      (node (ref "C151") (pin "2") (pinfunction "2_2") (pintype "passive"))
      (node (ref "C152") (pin "1") (pinfunction "1_1") (pintype "passive"))
      (node (ref "C153") (pin "2") (pinfunction "2_2") (pintype "passive"))
      (node (ref "R235") (pin "1") (pinfunction "1_1") (pintype "passive"))
      (node (ref "U29") (pin "6") (pinfunction "0V_6") (pintype "passive"))
    )
    (net (code "87") (name "S5") (class "Default")
      (node (ref "C100") (pin "1") (pinfunction "1_1") (pintype "passive"))
      (node (ref "C101") (pin "2") (pinfunction "2_2") (pintype "passive"))
      (node (ref "C98") (pin "1") (pinfunction "1_1") (pintype "passive"))
      (node (ref "C99") (pin "2") (pinfunction "2_2") (pintype "passive"))
      (node (ref "R233") (pin "1") (pinfunction "1_1") (pintype "passive"))
      (node (ref "U17") (pin "6") (pinfunction "0V_6") (pintype "passive"))
    )
    (net (code "88") (name "S6") (class "Default")
      (node (ref "C130") (pin "1") (pinfunction "1_1") (pintype "passive"))
      (node (ref "C131") (pin "2") (pinfunction "2_2") (pintype "passive"))
      (node (ref "C133") (pin "1") (pinfunction "1_1") (pintype "passive"))
      (node (ref "C134") (pin "2") (pinfunction "2_2") (pintype "passive"))
      (node (ref "R236") (pin "1") (pinfunction "1_1") (pintype "passive"))
      (node (ref "U25") (pin "6") (pinfunction "0V_6") (pintype "passive"))
    )
    (net (code "89") (name "U_HS_PWM") (class "Default")
      (node (ref "U13") (pin "6") (pinfunction "A5_6") (pintype "input"))
    )
    (net (code "90") (name "U_LS_PWM") (class "Default")
      (node (ref "U13") (pin "5") (pinfunction "A4_5") (pintype "input"))
    )
    (net (code "91") (name "V_HS_PWM") (class "Default")
      (node (ref "U13") (pin "3") (pinfunction "A2_3") (pintype "input"))
    )
    (net (code "92") (name "V_LS_PWM") (class "Default")
      (node (ref "U13") (pin "2") (pinfunction "A1_2") (pintype "input"))
    )
    (net (code "93") (name "W_HS_PWM") (class "Default")
      (node (ref "U13") (pin "9") (pinfunction "A8_9") (pintype "input"))
    )
    (net (code "94") (name "W_LS_PWM") (class "Default")
      (node (ref "U13") (pin "8") (pinfunction "A7_8") (pintype "input"))
    )
    (net (code "95") (name "unconnected-(U13-Y3-Pad16)") (class "Default")
      (node (ref "U13") (pin "16") (pinfunction "Y3_16") (pintype "tri_state"))
    )
    (net (code "96") (name "unconnected-(U13-Y6-Pad13)") (class "Default")
      (node (ref "U13") (pin "13") (pinfunction "Y6_13") (pintype "tri_state"))
    )
  )
)
